# io-board-f-5.net
KiCad netlist of a schematic drawn in EAGLE
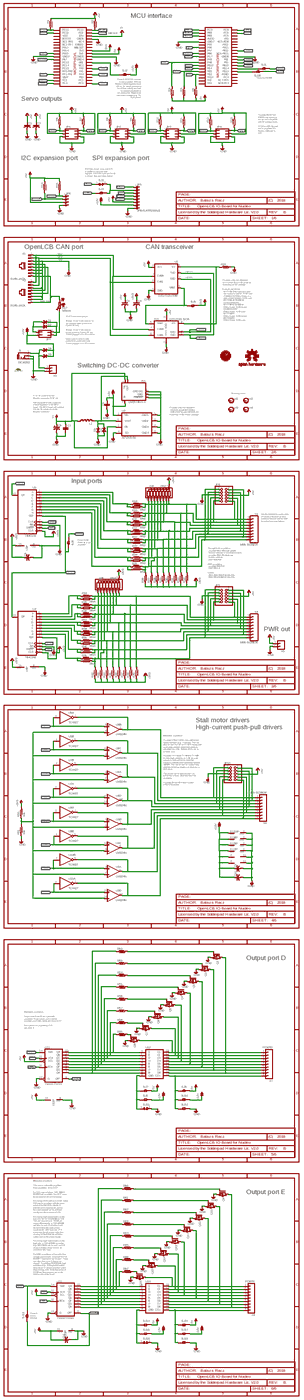
[diagram p0: schematic, sheet 1, overview]
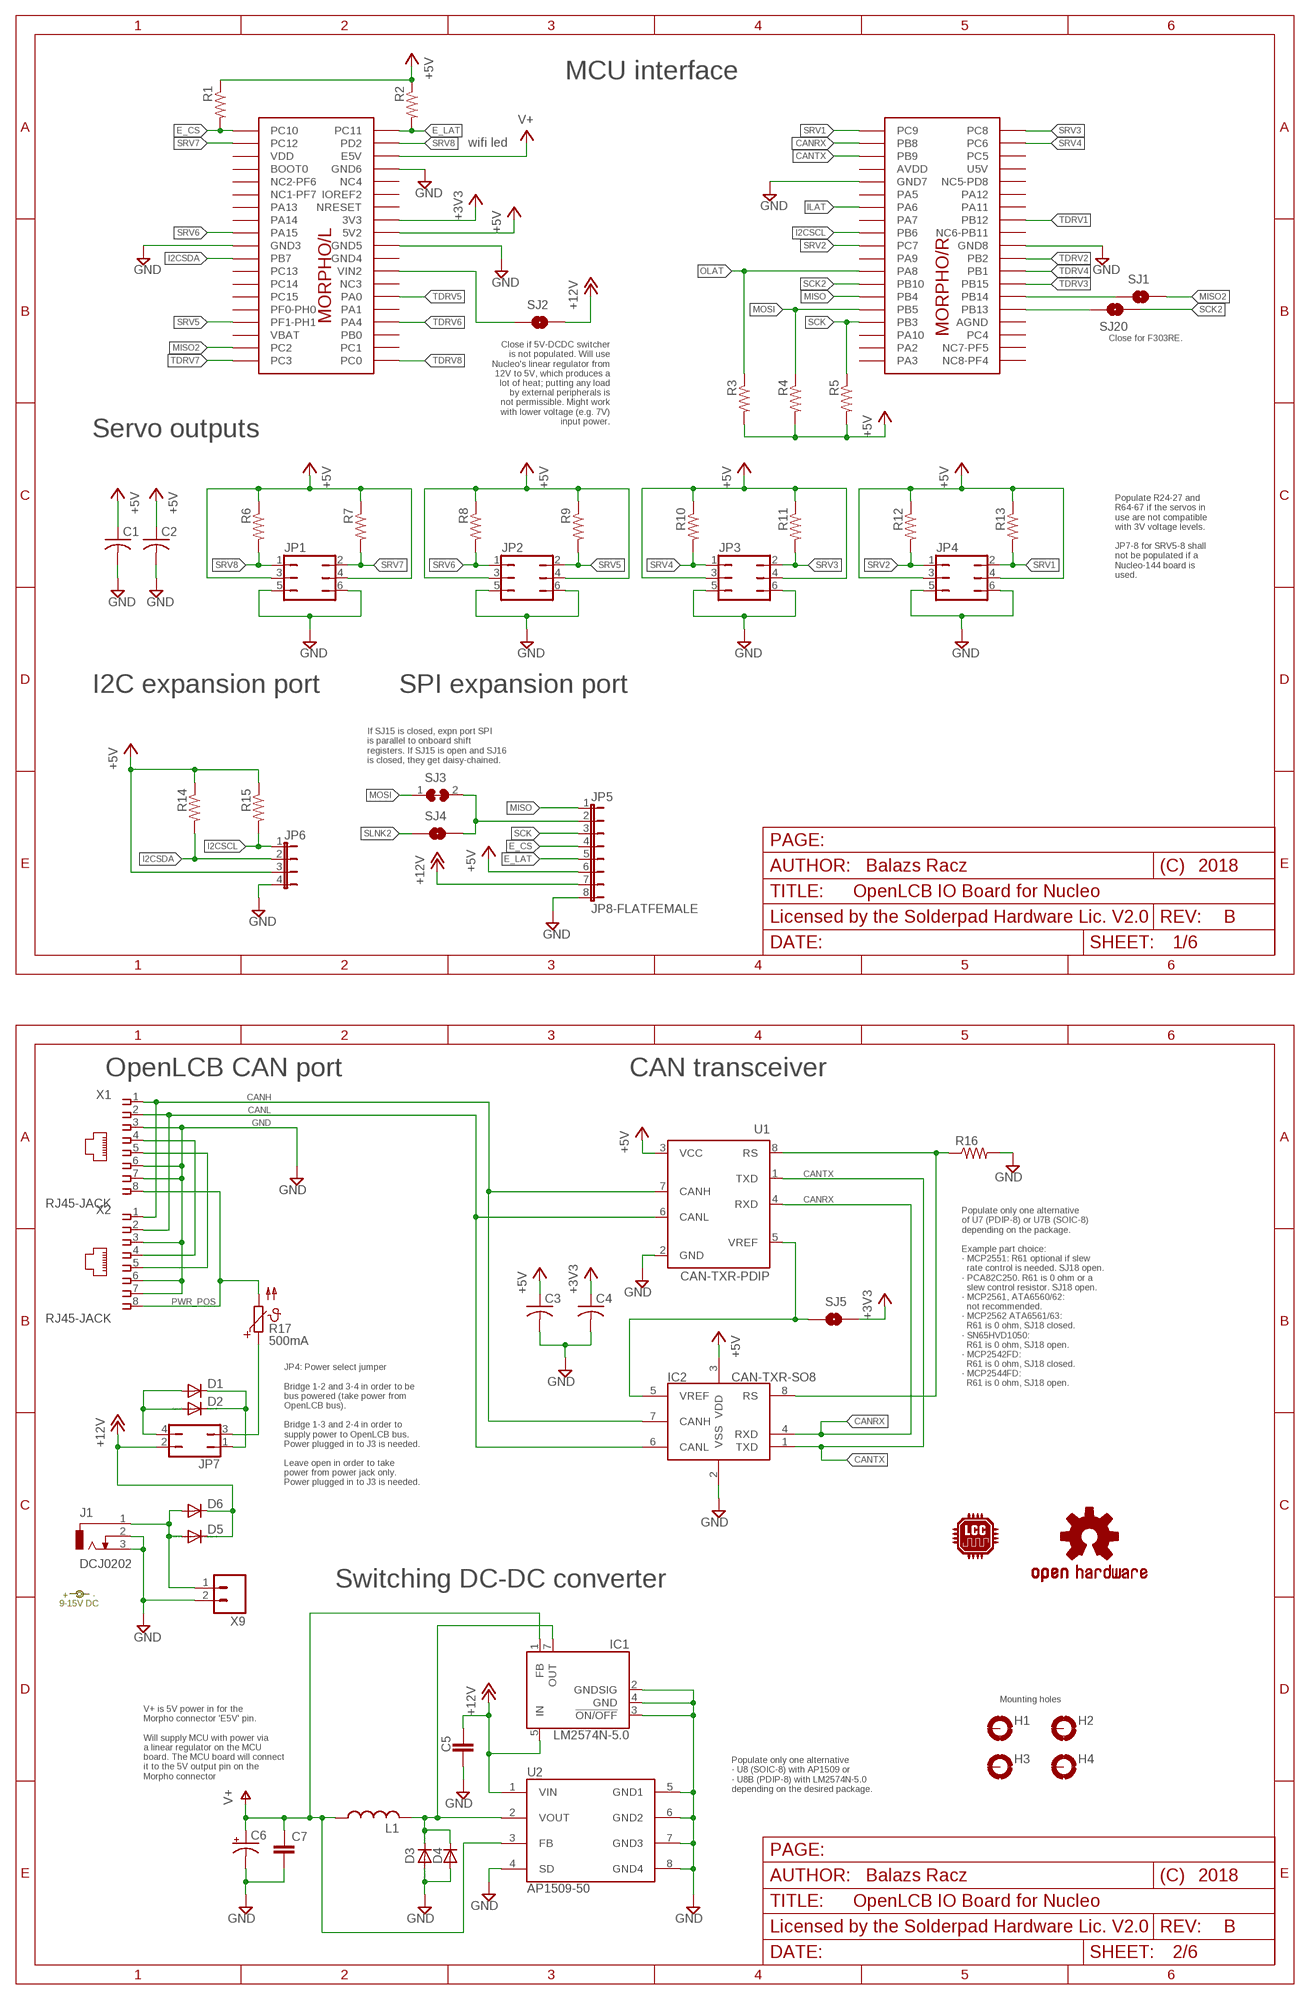
[diagram p1: schematic, sheet 1, part 1 of 4]
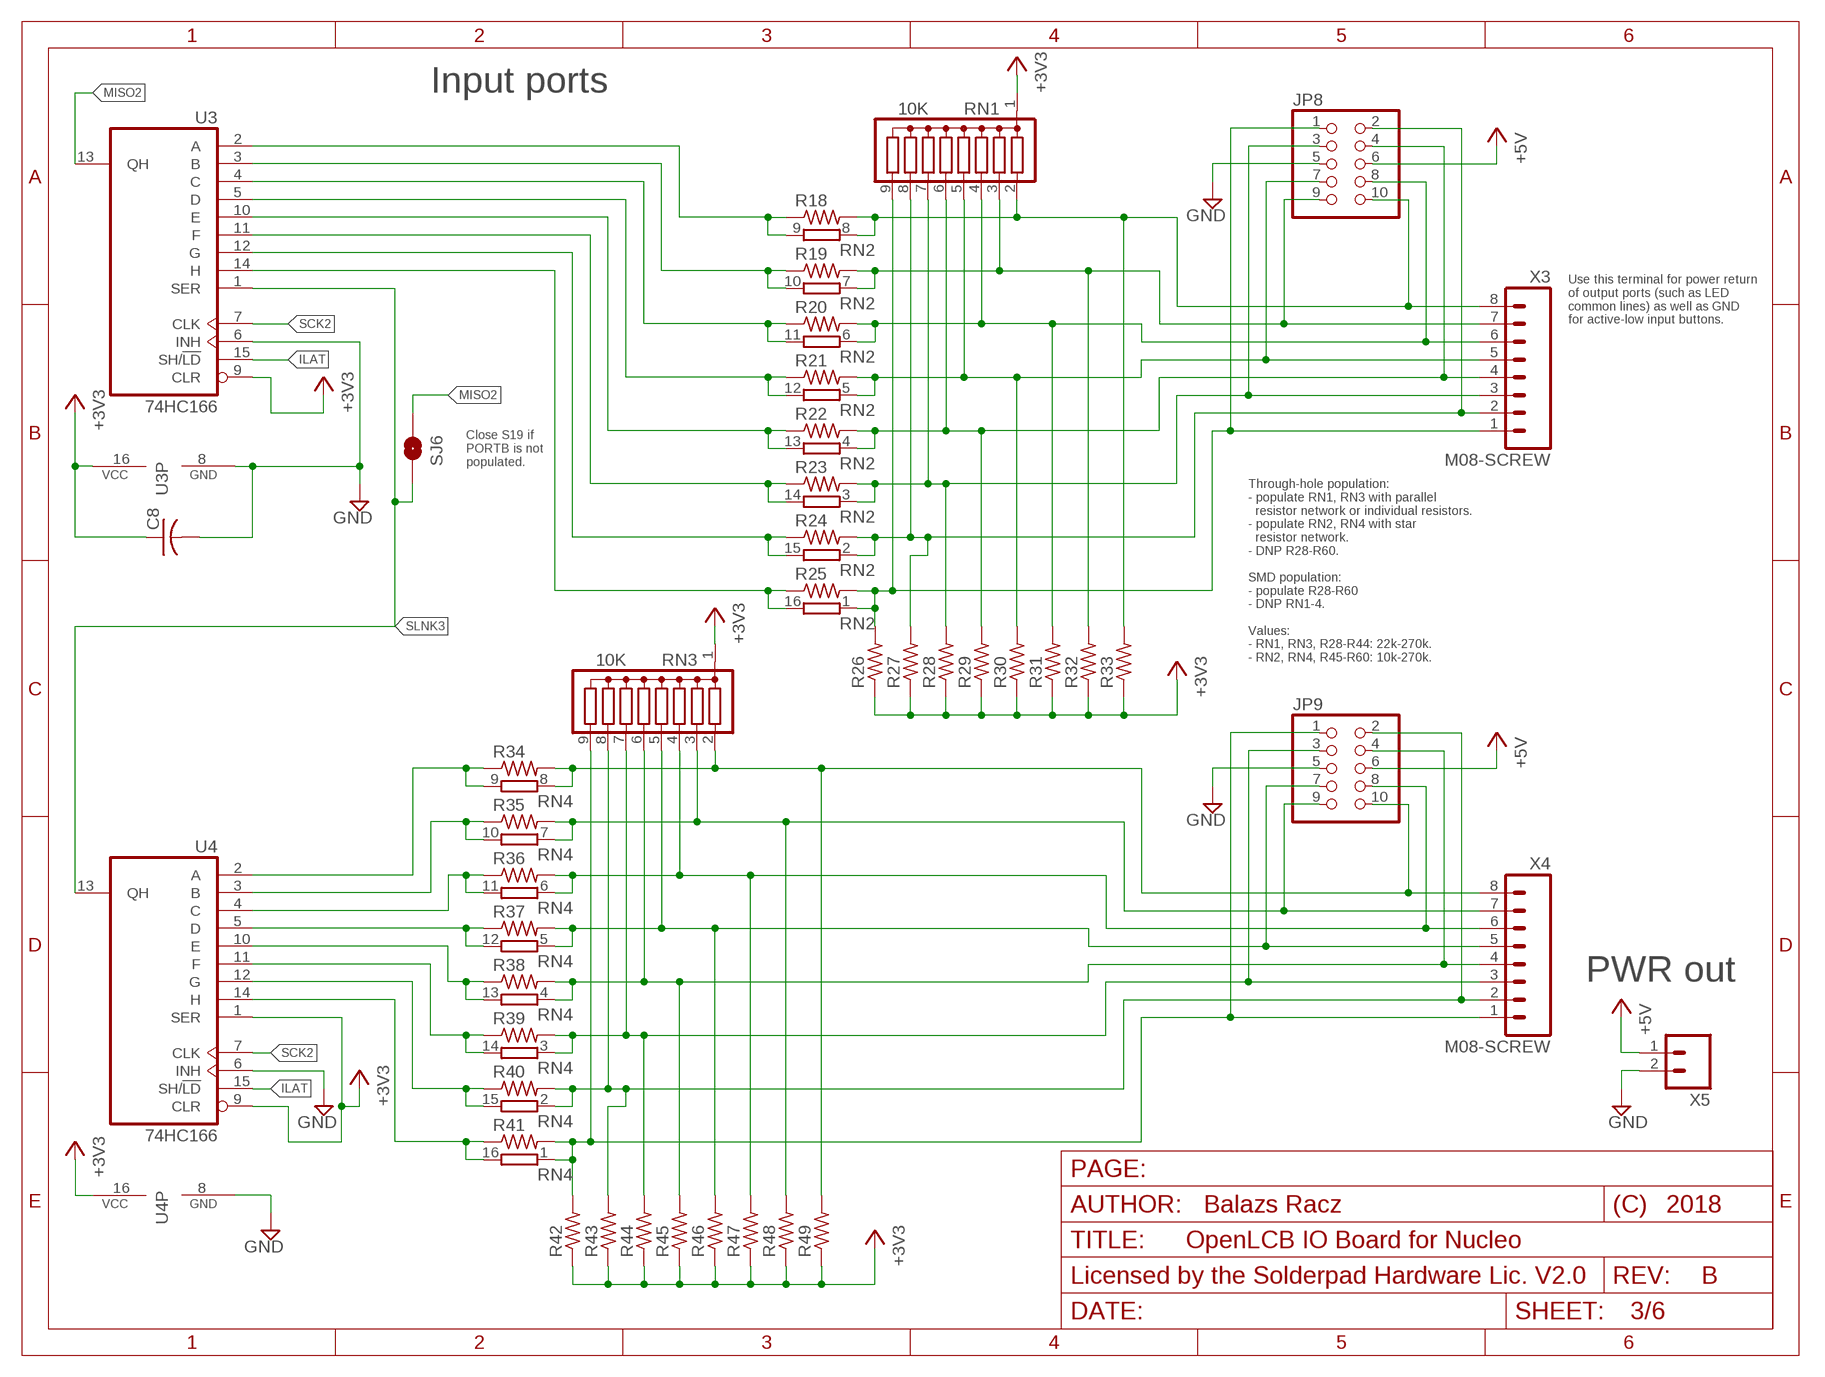
[diagram p2: schematic, sheet 1, part 2 of 4]
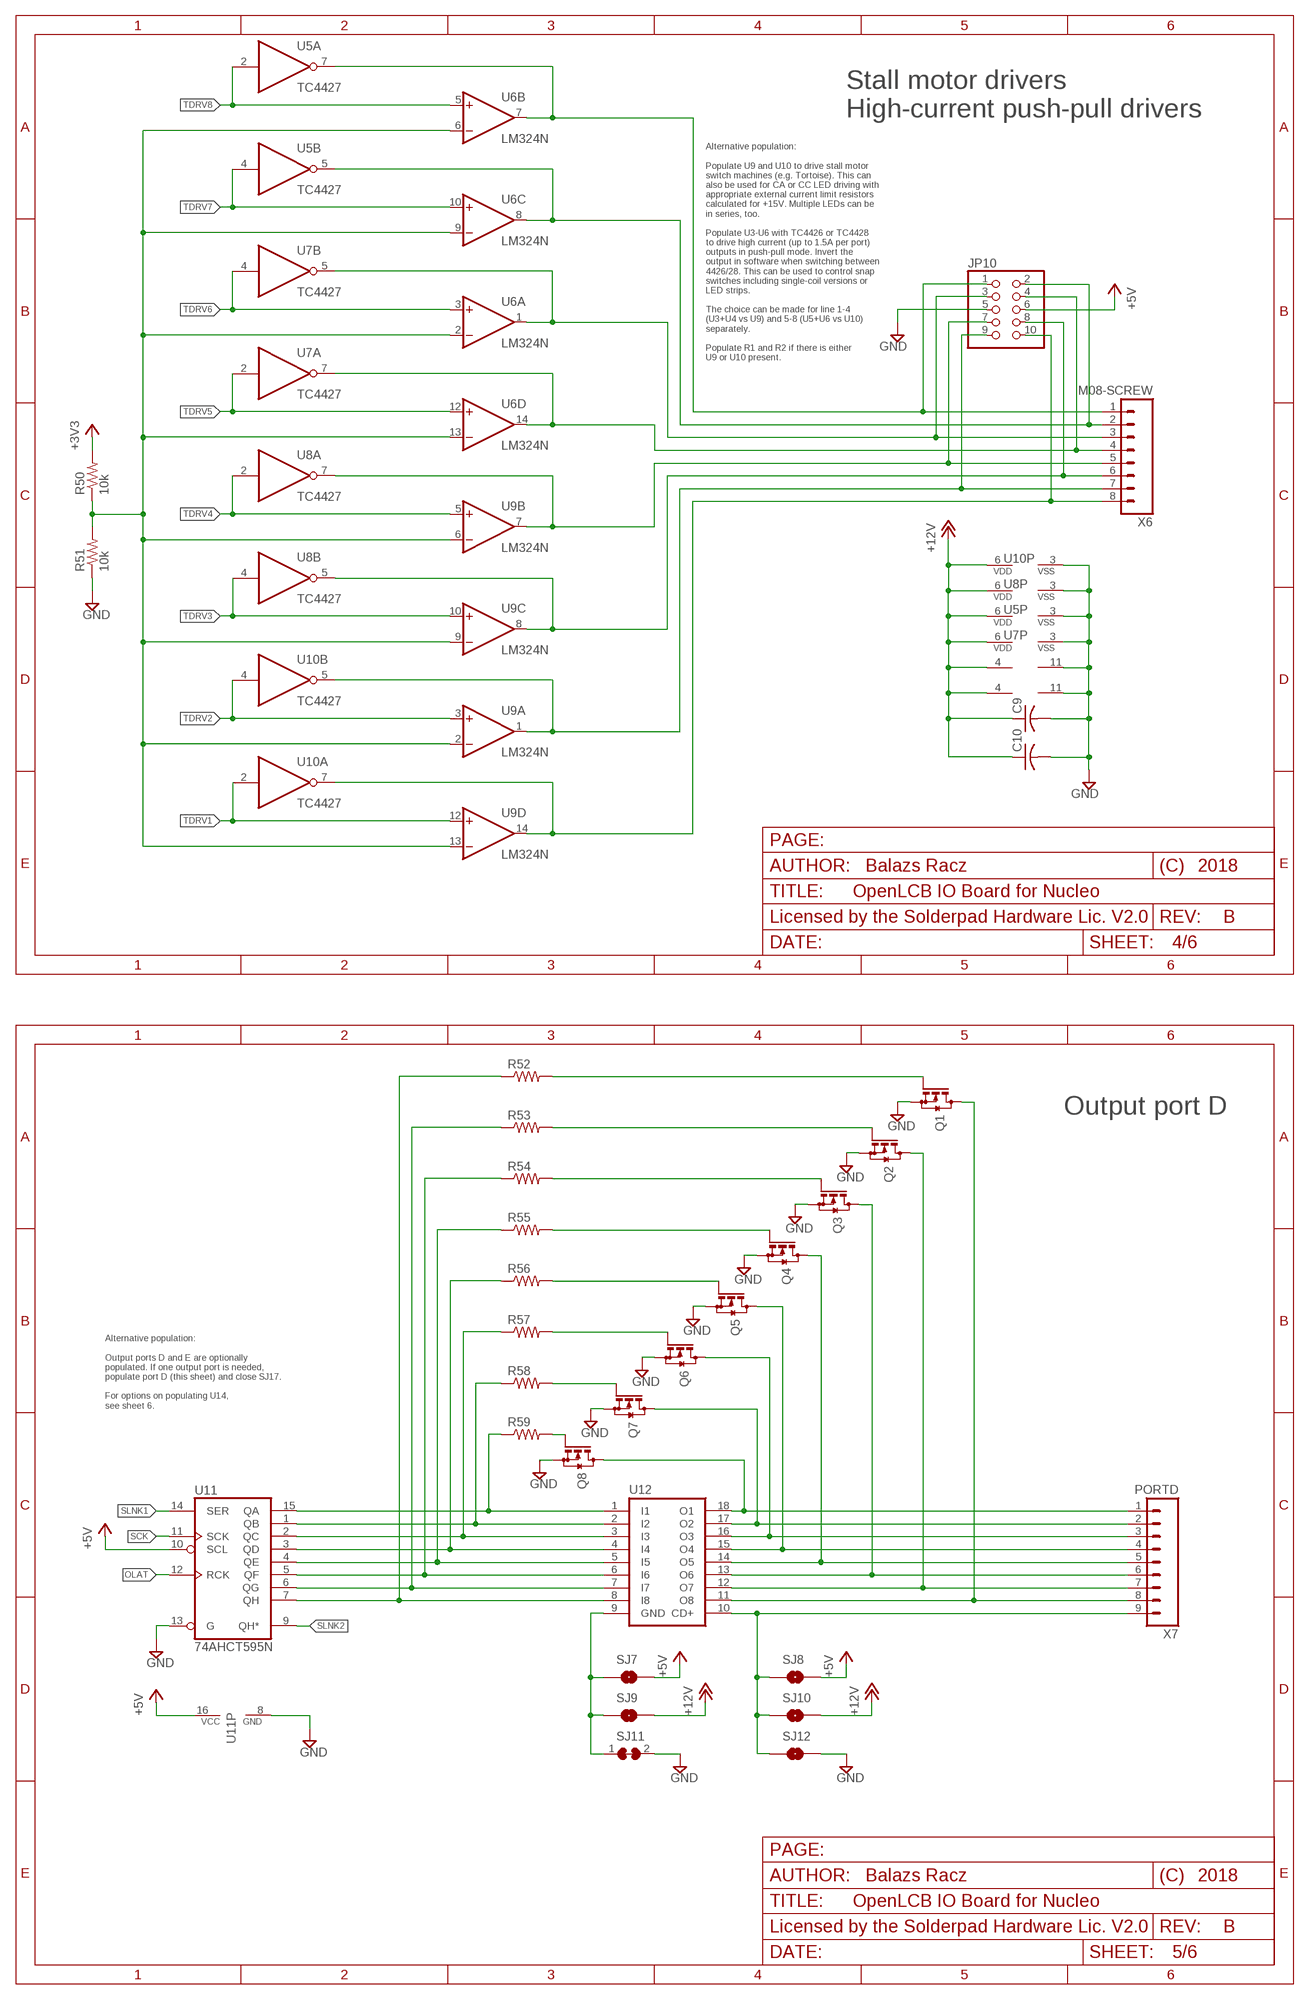
[diagram p3: schematic, sheet 1, part 3 of 4]
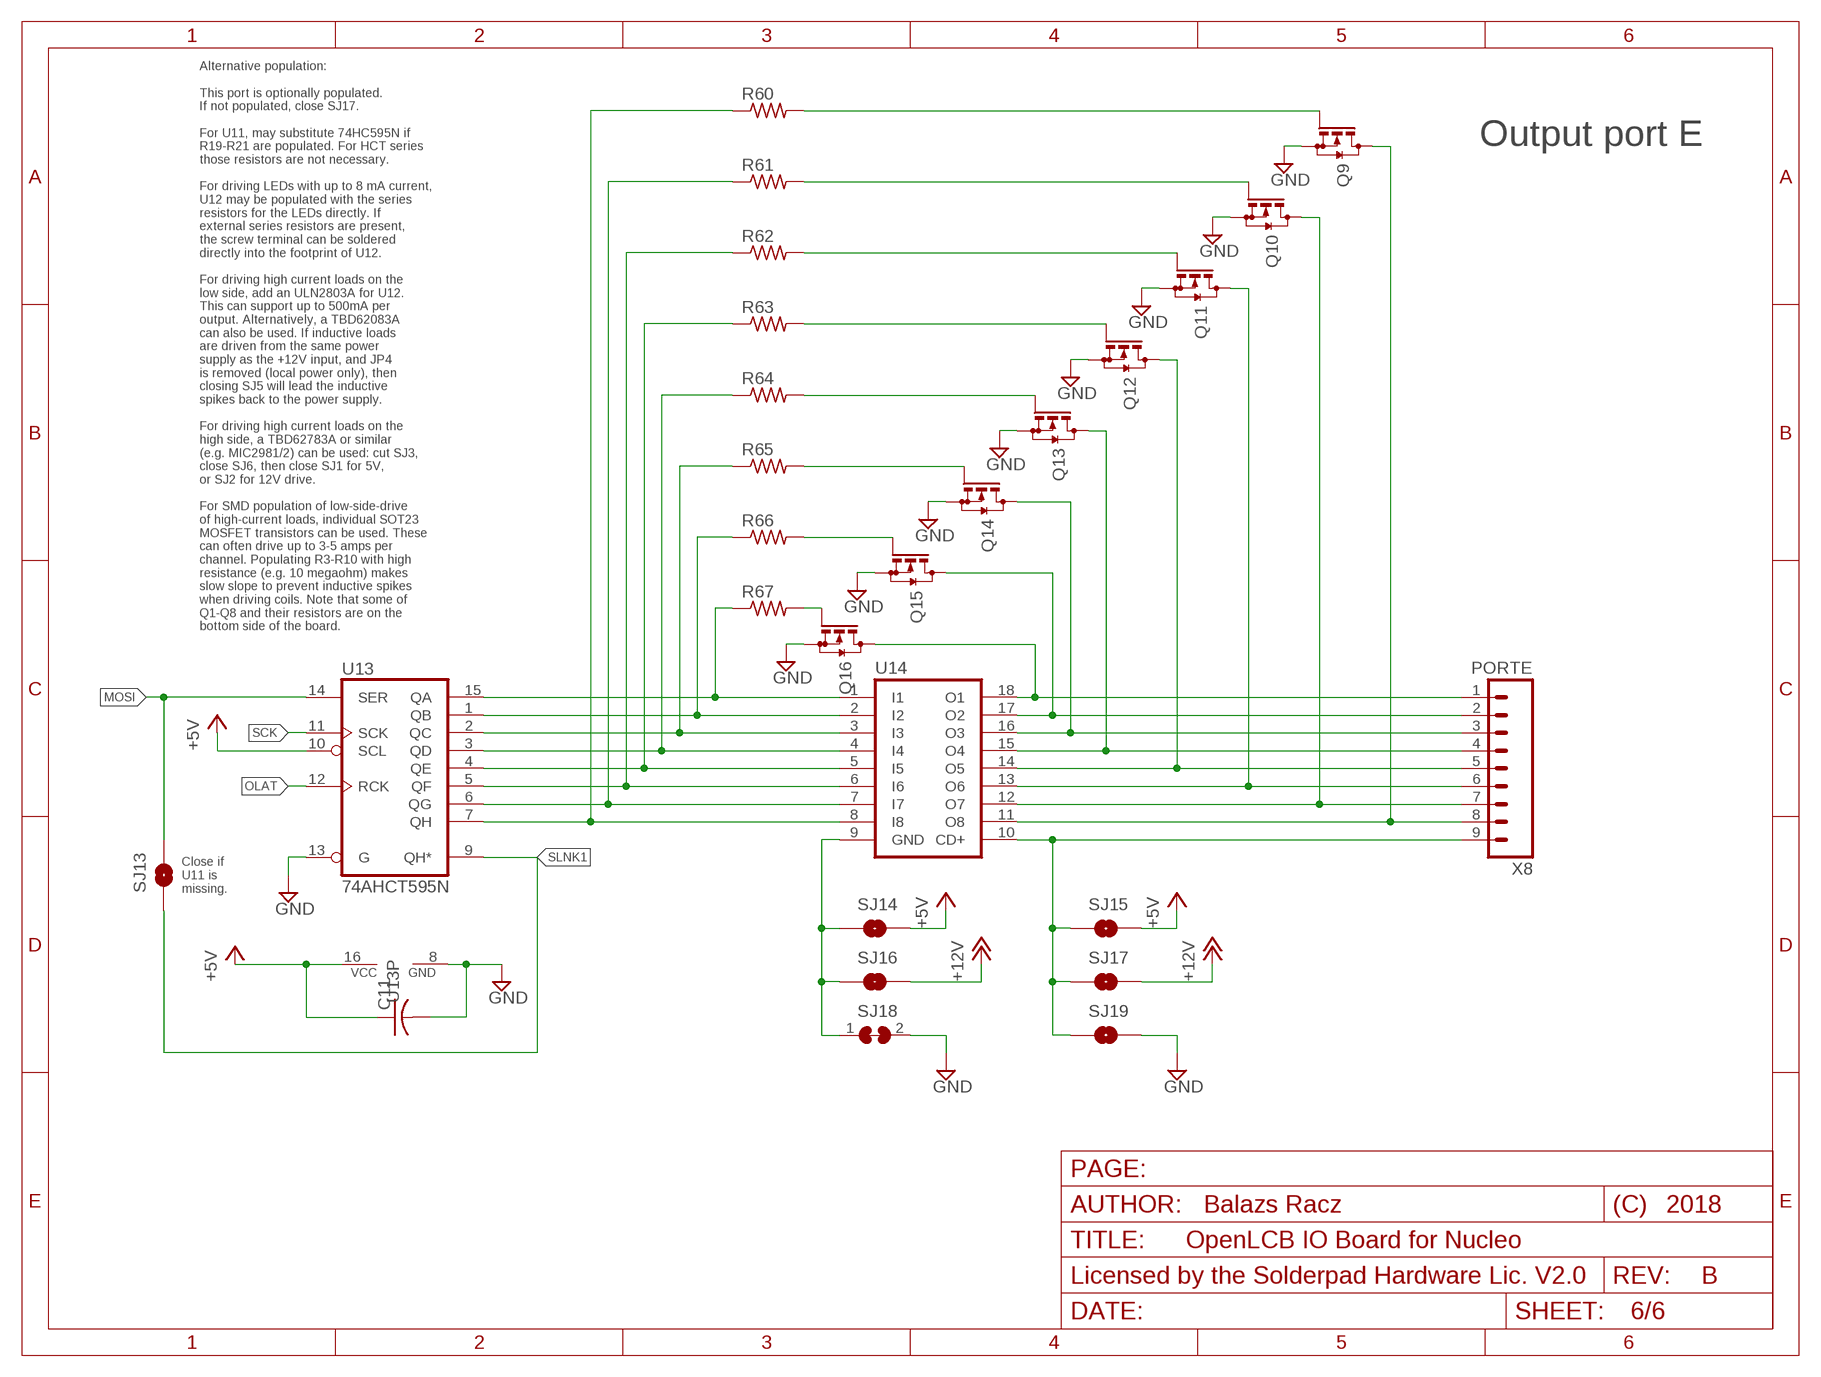
[diagram p4: schematic, sheet 1, part 4 of 4]

(export (version "E")
  (design (tool "Eeschema 10.0.6"))
  (components
    (comp (ref "C1")
      (value "C-USC1206")
      (footprint "eagle-import:C1206")
      (libsource (lib "eagle-import") (part "C-USC1206"))
    )
    (comp (ref "C2")
      (value "C-USC1206")
      (footprint "eagle-import:C1206")
      (libsource (lib "eagle-import") (part "C-USC1206"))
    )
    (comp (ref "C3")
      (value "C-USC0805")
      (footprint "eagle-import:C0805")
      (libsource (lib "eagle-import") (part "C-USC0805"))
    )
    (comp (ref "C4")
      (value "C-USC0805")
      (footprint "eagle-import:C0805")
      (libsource (lib "eagle-import") (part "C-USC0805"))
    )
    (comp (ref "C5")
      (value "C-EUC1206")
      (footprint "eagle-import:C1206")
      (libsource (lib "eagle-import") (part "C-EUC1206"))
    )
    (comp (ref "C6")
      (value "CPOL-USE2.5-5")
      (footprint "eagle-import:E2,5-5")
      (libsource (lib "eagle-import") (part "CPOL-USE2.5-5"))
    )
    (comp (ref "C7")
      (value "C-EUC1206")
      (footprint "eagle-import:C1206")
      (libsource (lib "eagle-import") (part "C-EUC1206"))
    )
    (comp (ref "C8")
      (value "C-USC0805")
      (footprint "eagle-import:C0805")
      (libsource (lib "eagle-import") (part "C-USC0805"))
    )
    (comp (ref "C9")
      (value "C-USC1206")
      (footprint "eagle-import:C1206")
      (libsource (lib "eagle-import") (part "C-USC1206"))
    )
    (comp (ref "C10")
      (value "C-USC1206")
      (footprint "eagle-import:C1206")
      (libsource (lib "eagle-import") (part "C-USC1206"))
    )
    (comp (ref "C11")
      (value "C-USC0805")
      (footprint "eagle-import:C0805")
      (libsource (lib "eagle-import") (part "C-USC0805"))
    )
    (comp (ref "D1")
      (value "DIODEDO-214AA-NODOC")
      (footprint "eagle-import:DO214AA-NODOC")
      (libsource (lib "eagle-import") (part "DIODEDO-214AA-NODOC"))
    )
    (comp (ref "D2")
      (value "DIODE-DO41-7.6")
      (footprint "eagle-import:DO41-7.6")
      (libsource (lib "eagle-import") (part "DIODE-DO41-7.6"))
    )
    (comp (ref "D3")
      (value "DIODE-DO41-7.6")
      (footprint "eagle-import:DO41-7.6")
      (libsource (lib "eagle-import") (part "DIODE-DO41-7.6"))
    )
    (comp (ref "D4")
      (value "DIODEDO-214AA-NODOC")
      (footprint "eagle-import:DO214AA-NODOC")
      (libsource (lib "eagle-import") (part "DIODEDO-214AA-NODOC"))
    )
    (comp (ref "D5")
      (value "DIODE-DO41-7.6")
      (footprint "eagle-import:DO41-7.6")
      (libsource (lib "eagle-import") (part "DIODE-DO41-7.6"))
    )
    (comp (ref "D6")
      (value "DIODEDO-214AA-NODOC")
      (footprint "eagle-import:DO214AA-NODOC")
      (libsource (lib "eagle-import") (part "DIODEDO-214AA-NODOC"))
    )
    (comp (ref "G1")
      (value "NUCLEO_64_GENERIC")
      (footprint "eagle-import:NUCLEO_BRD_BASE64")
      (libsource (lib "eagle-import") (part "NUCLEO_64_GENERIC"))
    )
    (comp (ref "H1")
      (value "MOUNT-PAD-ROUND3.3")
      (footprint "eagle-import:3,3-PAD")
      (libsource (lib "eagle-import") (part "MOUNT-PAD-ROUND3.3"))
    )
    (comp (ref "H2")
      (value "MOUNT-PAD-ROUND3.3")
      (footprint "eagle-import:3,3-PAD")
      (libsource (lib "eagle-import") (part "MOUNT-PAD-ROUND3.3"))
    )
    (comp (ref "H3")
      (value "MOUNT-PAD-ROUND3.3")
      (footprint "eagle-import:3,3-PAD")
      (libsource (lib "eagle-import") (part "MOUNT-PAD-ROUND3.3"))
    )
    (comp (ref "H4")
      (value "MOUNT-PAD-ROUND3.3")
      (footprint "eagle-import:3,3-PAD")
      (libsource (lib "eagle-import") (part "MOUNT-PAD-ROUND3.3"))
    )
    (comp (ref "IC1")
      (value "LM2574N-5.0")
      (footprint "eagle-import:DIL08")
      (libsource (lib "eagle-import") (part "LM2574?-N5.0"))
    )
    (comp (ref "IC2")
      (value "CAN-TXR-SO8")
      (footprint "eagle-import:SO-08")
      (libsource (lib "eagle-import") (part "MCP2551-SN"))
    )
    (comp (ref "J1")
      (value "DCJ0202")
      (footprint "eagle-import:DCJ0202")
      (libsource (lib "eagle-import") (part "DCJ0202"))
    )
    (comp (ref "JP1")
      (value "JP3Q")
      (footprint "eagle-import:JP3Q")
      (libsource (lib "eagle-import") (part "JP3Q"))
    )
    (comp (ref "JP2")
      (value "JP3Q")
      (footprint "eagle-import:JP3Q")
      (libsource (lib "eagle-import") (part "JP3Q"))
    )
    (comp (ref "JP3")
      (value "JP3Q")
      (footprint "eagle-import:JP3Q")
      (libsource (lib "eagle-import") (part "JP3Q"))
    )
    (comp (ref "JP4")
      (value "JP3Q")
      (footprint "eagle-import:JP3Q")
      (libsource (lib "eagle-import") (part "JP3Q"))
    )
    (comp (ref "JP5")
      (value "JP8-FLATFEMALE")
      (footprint "eagle-import:JP8F-FEM")
      (libsource (lib "eagle-import") (part "JP8-FLATFEMALE"))
    )
    (comp (ref "JP6")
      (value "JP4-FLAT")
      (footprint "eagle-import:JP4F")
      (libsource (lib "eagle-import") (part "JP4-FLAT"))
    )
    (comp (ref "JP7")
      (value "JP2Q")
      (footprint "eagle-import:JP2Q")
      (libsource (lib "eagle-import") (part "JP2Q"))
    )
    (comp (ref "JP8")
      (value "PINHD-2X5CN")
      (footprint "eagle-import:CON10M")
      (libsource (lib "eagle-import") (part "PINHD-2X5CN"))
    )
    (comp (ref "JP9")
      (value "PINHD-2X5CN")
      (footprint "eagle-import:CON10M")
      (libsource (lib "eagle-import") (part "PINHD-2X5CN"))
    )
    (comp (ref "JP10")
      (value "PINHD-2X5CN")
      (footprint "eagle-import:CON10M")
      (libsource (lib "eagle-import") (part "PINHD-2X5CN"))
    )
    (comp (ref "L1")
      (value "L-US")
      (footprint "eagle-import:L5-8,5")
      (libsource (lib "eagle-import") (part "L-US"))
    )
    (comp (ref "LG1")
      (value "LCC_LOGO")
      (footprint "eagle-import:LCC_LOGO")
      (libsource (lib "eagle-import") (part "LCC_LOGO"))
    )
    (comp (ref "LOGO1")
      (value "DOC-OSHW-LOGOM")
      (footprint "eagle-import:OSHW-LOGO-M")
      (libsource (lib "eagle-import") (part "DOC-OSHW-LOGOM"))
    )
    (comp (ref "P1")
      (value "9-15V DC")
      (footprint "eagle-import:POWER_USAGE")
      (libsource (lib "eagle-import") (part "DOC-POWER_LABEL"))
    )
    (comp (ref "Q1")
      (value "BSS123")
      (footprint "eagle-import:SOT23")
      (libsource (lib "eagle-import") (part "BSS123"))
    )
    (comp (ref "Q2")
      (value "BSS123")
      (footprint "eagle-import:SOT23")
      (libsource (lib "eagle-import") (part "BSS123"))
    )
    (comp (ref "Q3")
      (value "BSS123")
      (footprint "eagle-import:SOT23")
      (libsource (lib "eagle-import") (part "BSS123"))
    )
    (comp (ref "Q4")
      (value "BSS123")
      (footprint "eagle-import:SOT23")
      (libsource (lib "eagle-import") (part "BSS123"))
    )
    (comp (ref "Q5")
      (value "BSS123")
      (footprint "eagle-import:SOT23")
      (libsource (lib "eagle-import") (part "BSS123"))
    )
    (comp (ref "Q6")
      (value "BSS123")
      (footprint "eagle-import:SOT23")
      (libsource (lib "eagle-import") (part "BSS123"))
    )
    (comp (ref "Q7")
      (value "BSS123")
      (footprint "eagle-import:SOT23")
      (libsource (lib "eagle-import") (part "BSS123"))
    )
    (comp (ref "Q8")
      (value "BSS123")
      (footprint "eagle-import:SOT23")
      (libsource (lib "eagle-import") (part "BSS123"))
    )
    (comp (ref "Q9")
      (value "BSS123")
      (footprint "eagle-import:SOT23")
      (libsource (lib "eagle-import") (part "BSS123"))
    )
    (comp (ref "Q10")
      (value "BSS123")
      (footprint "eagle-import:SOT23")
      (libsource (lib "eagle-import") (part "BSS123"))
    )
    (comp (ref "Q11")
      (value "BSS123")
      (footprint "eagle-import:SOT23")
      (libsource (lib "eagle-import") (part "BSS123"))
    )
    (comp (ref "Q12")
      (value "BSS123")
      (footprint "eagle-import:SOT23")
      (libsource (lib "eagle-import") (part "BSS123"))
    )
    (comp (ref "Q13")
      (value "BSS123")
      (footprint "eagle-import:SOT23")
      (libsource (lib "eagle-import") (part "BSS123"))
    )
    (comp (ref "Q14")
      (value "BSS123")
      (footprint "eagle-import:SOT23")
      (libsource (lib "eagle-import") (part "BSS123"))
    )
    (comp (ref "Q15")
      (value "BSS123")
      (footprint "eagle-import:SOT23")
      (libsource (lib "eagle-import") (part "BSS123"))
    )
    (comp (ref "Q16")
      (value "BSS123")
      (footprint "eagle-import:SOT23")
      (libsource (lib "eagle-import") (part "BSS123"))
    )
    (comp (ref "R1")
      (value "R-US_R0805")
      (footprint "eagle-import:R0805")
      (libsource (lib "eagle-import") (part "rcl_334_R-US_R0805"))
    )
    (comp (ref "R2")
      (value "R-US_R0805")
      (footprint "eagle-import:R0805")
      (libsource (lib "eagle-import") (part "rcl_334_R-US_R0805"))
    )
    (comp (ref "R3")
      (value "R-US_R0805")
      (footprint "eagle-import:R0805")
      (libsource (lib "eagle-import") (part "rcl_334_R-US_R0805"))
    )
    (comp (ref "R4")
      (value "R-US_R0805")
      (footprint "eagle-import:R0805")
      (libsource (lib "eagle-import") (part "rcl_334_R-US_R0805"))
    )
    (comp (ref "R5")
      (value "R-US_R0805")
      (footprint "eagle-import:R0805")
      (libsource (lib "eagle-import") (part "rcl_334_R-US_R0805"))
    )
    (comp (ref "R6")
      (value "R-US_R0805")
      (footprint "eagle-import:R0805")
      (libsource (lib "eagle-import") (part "rcl_334_R-US_R0805"))
    )
    (comp (ref "R7")
      (value "R-US_R0805")
      (footprint "eagle-import:R0805")
      (libsource (lib "eagle-import") (part "rcl_334_R-US_R0805"))
    )
    (comp (ref "R8")
      (value "R-US_R0805")
      (footprint "eagle-import:R0805")
      (libsource (lib "eagle-import") (part "rcl_334_R-US_R0805"))
    )
    (comp (ref "R9")
      (value "R-US_R0805")
      (footprint "eagle-import:R0805")
      (libsource (lib "eagle-import") (part "rcl_334_R-US_R0805"))
    )
    (comp (ref "R10")
      (value "R-US_R0805")
      (footprint "eagle-import:R0805")
      (libsource (lib "eagle-import") (part "rcl_334_R-US_R0805"))
    )
    (comp (ref "R11")
      (value "R-US_R0805")
      (footprint "eagle-import:R0805")
      (libsource (lib "eagle-import") (part "rcl_334_R-US_R0805"))
    )
    (comp (ref "R12")
      (value "R-US_R0805")
      (footprint "eagle-import:R0805")
      (libsource (lib "eagle-import") (part "rcl_334_R-US_R0805"))
    )
    (comp (ref "R13")
      (value "R-US_R0805")
      (footprint "eagle-import:R0805")
      (libsource (lib "eagle-import") (part "rcl_334_R-US_R0805"))
    )
    (comp (ref "R14")
      (value "R-US_R0805")
      (footprint "eagle-import:R0805")
      (libsource (lib "eagle-import") (part "rcl_334_R-US_R0805"))
    )
    (comp (ref "R15")
      (value "R-US_R0805")
      (footprint "eagle-import:R0805")
      (libsource (lib "eagle-import") (part "rcl_334_R-US_R0805"))
    )
    (comp (ref "R16")
      (value "R-US_R0805")
      (footprint "eagle-import:R0805")
      (libsource (lib "eagle-import") (part "rcl_334_R-US_R0805"))
    )
    (comp (ref "R17")
      (value "500mA")
      (footprint "eagle-import:PTC1812")
      (libsource (lib "eagle-import") (part "PTC_1812"))
    )
    (comp (ref "R18")
      (value "R-US_R0603")
      (footprint "eagle-import:R0603")
      (libsource (lib "eagle-import") (part "rcl_334_R-US_R0603"))
    )
    (comp (ref "R19")
      (value "R-US_R0603")
      (footprint "eagle-import:R0603")
      (libsource (lib "eagle-import") (part "rcl_334_R-US_R0603"))
    )
    (comp (ref "R20")
      (value "R-US_R0603")
      (footprint "eagle-import:R0603")
      (libsource (lib "eagle-import") (part "rcl_334_R-US_R0603"))
    )
    (comp (ref "R21")
      (value "R-US_R0603")
      (footprint "eagle-import:R0603")
      (libsource (lib "eagle-import") (part "rcl_334_R-US_R0603"))
    )
    (comp (ref "R22")
      (value "R-US_R0603")
      (footprint "eagle-import:R0603")
      (libsource (lib "eagle-import") (part "rcl_334_R-US_R0603"))
    )
    (comp (ref "R23")
      (value "R-US_R0603")
      (footprint "eagle-import:R0603")
      (libsource (lib "eagle-import") (part "rcl_334_R-US_R0603"))
    )
    (comp (ref "R24")
      (value "R-US_R0603")
      (footprint "eagle-import:R0603")
      (libsource (lib "eagle-import") (part "rcl_334_R-US_R0603"))
    )
    (comp (ref "R25")
      (value "R-US_R0603")
      (footprint "eagle-import:R0603")
      (libsource (lib "eagle-import") (part "rcl_334_R-US_R0603"))
    )
    (comp (ref "R26")
      (value "R-US")
      (footprint "eagle-import:R0603")
      (libsource (lib "eagle-import") (part "R-US"))
    )
    (comp (ref "R27")
      (value "R-US")
      (footprint "eagle-import:R0603")
      (libsource (lib "eagle-import") (part "R-US"))
    )
    (comp (ref "R28")
      (value "R-US")
      (footprint "eagle-import:R0603")
      (libsource (lib "eagle-import") (part "R-US"))
    )
    (comp (ref "R29")
      (value "R-US")
      (footprint "eagle-import:R0603")
      (libsource (lib "eagle-import") (part "R-US"))
    )
    (comp (ref "R30")
      (value "R-US")
      (footprint "eagle-import:R0603")
      (libsource (lib "eagle-import") (part "R-US"))
    )
    (comp (ref "R31")
      (value "R-US")
      (footprint "eagle-import:R0603")
      (libsource (lib "eagle-import") (part "R-US"))
    )
    (comp (ref "R32")
      (value "R-US")
      (footprint "eagle-import:R0603")
      (libsource (lib "eagle-import") (part "R-US"))
    )
    (comp (ref "R33")
      (value "R-US")
      (footprint "eagle-import:R0603")
      (libsource (lib "eagle-import") (part "R-US"))
    )
    (comp (ref "R34")
      (value "R-US_R0603")
      (footprint "eagle-import:R0603")
      (libsource (lib "eagle-import") (part "rcl_334_R-US_R0603"))
    )
    (comp (ref "R35")
      (value "R-US_R0603")
      (footprint "eagle-import:R0603")
      (libsource (lib "eagle-import") (part "rcl_334_R-US_R0603"))
    )
    (comp (ref "R36")
      (value "R-US_R0603")
      (footprint "eagle-import:R0603")
      (libsource (lib "eagle-import") (part "rcl_334_R-US_R0603"))
    )
    (comp (ref "R37")
      (value "R-US_R0603")
      (footprint "eagle-import:R0603")
      (libsource (lib "eagle-import") (part "rcl_334_R-US_R0603"))
    )
    (comp (ref "R38")
      (value "R-US_R0603")
      (footprint "eagle-import:R0603")
      (libsource (lib "eagle-import") (part "rcl_334_R-US_R0603"))
    )
    (comp (ref "R39")
      (value "R-US_R0603")
      (footprint "eagle-import:R0603")
      (libsource (lib "eagle-import") (part "rcl_334_R-US_R0603"))
    )
    (comp (ref "R40")
      (value "R-US_R0603")
      (footprint "eagle-import:R0603")
      (libsource (lib "eagle-import") (part "rcl_334_R-US_R0603"))
    )
    (comp (ref "R41")
      (value "R-US_R0603")
      (footprint "eagle-import:R0603")
      (libsource (lib "eagle-import") (part "rcl_334_R-US_R0603"))
    )
    (comp (ref "R42")
      (value "R-US")
      (footprint "eagle-import:R0603")
      (libsource (lib "eagle-import") (part "R-US"))
    )
    (comp (ref "R43")
      (value "R-US")
      (footprint "eagle-import:R0603")
      (libsource (lib "eagle-import") (part "R-US"))
    )
    (comp (ref "R44")
      (value "R-US")
      (footprint "eagle-import:R0603")
      (libsource (lib "eagle-import") (part "R-US"))
    )
    (comp (ref "R45")
      (value "R-US")
      (footprint "eagle-import:R0603")
      (libsource (lib "eagle-import") (part "R-US"))
    )
    (comp (ref "R46")
      (value "R-US")
      (footprint "eagle-import:R0603")
      (libsource (lib "eagle-import") (part "R-US"))
    )
    (comp (ref "R47")
      (value "R-US")
      (footprint "eagle-import:R0603")
      (libsource (lib "eagle-import") (part "R-US"))
    )
    (comp (ref "R48")
      (value "R-US")
      (footprint "eagle-import:R0603")
      (libsource (lib "eagle-import") (part "R-US"))
    )
    (comp (ref "R49")
      (value "R-US")
      (footprint "eagle-import:R0603")
      (libsource (lib "eagle-import") (part "R-US"))
    )
    (comp (ref "R50")
      (value "10k")
      (footprint "eagle-import:R0805")
      (libsource (lib "eagle-import") (part "R-US_R0805"))
    )
    (comp (ref "R51")
      (value "10k")
      (footprint "eagle-import:R0805")
      (libsource (lib "eagle-import") (part "R-US_R0805"))
    )
    (comp (ref "R52")
      (value "R-US_R0603")
      (footprint "eagle-import:R0603")
      (libsource (lib "eagle-import") (part "R-US_R0603"))
    )
    (comp (ref "R53")
      (value "R-US_R0603")
      (footprint "eagle-import:R0603")
      (libsource (lib "eagle-import") (part "R-US_R0603"))
    )
    (comp (ref "R54")
      (value "R-US_R0603")
      (footprint "eagle-import:R0603")
      (libsource (lib "eagle-import") (part "R-US_R0603"))
    )
    (comp (ref "R55")
      (value "R-US_R0603")
      (footprint "eagle-import:R0603")
      (libsource (lib "eagle-import") (part "R-US_R0603"))
    )
    (comp (ref "R56")
      (value "R-US_R0603")
      (footprint "eagle-import:R0603")
      (libsource (lib "eagle-import") (part "R-US_R0603"))
    )
    (comp (ref "R57")
      (value "R-US_R0603")
      (footprint "eagle-import:R0603")
      (libsource (lib "eagle-import") (part "R-US_R0603"))
    )
    (comp (ref "R58")
      (value "R-US_R0603")
      (footprint "eagle-import:R0603")
      (libsource (lib "eagle-import") (part "R-US_R0603"))
    )
    (comp (ref "R59")
      (value "R-US_R0603")
      (footprint "eagle-import:R0603")
      (libsource (lib "eagle-import") (part "R-US_R0603"))
    )
    (comp (ref "R60")
      (value "R-US_R0603")
      (footprint "eagle-import:R0603")
      (libsource (lib "eagle-import") (part "R-US_R0603"))
    )
    (comp (ref "R61")
      (value "R-US_R0603")
      (footprint "eagle-import:R0603")
      (libsource (lib "eagle-import") (part "R-US_R0603"))
    )
    (comp (ref "R62")
      (value "R-US_R0603")
      (footprint "eagle-import:R0603")
      (libsource (lib "eagle-import") (part "R-US_R0603"))
    )
    (comp (ref "R63")
      (value "R-US_R0603")
      (footprint "eagle-import:R0603")
      (libsource (lib "eagle-import") (part "R-US_R0603"))
    )
    (comp (ref "R64")
      (value "R-US_R0603")
      (footprint "eagle-import:R0603")
      (libsource (lib "eagle-import") (part "R-US_R0603"))
    )
    (comp (ref "R65")
      (value "R-US_R0603")
      (footprint "eagle-import:R0603")
      (libsource (lib "eagle-import") (part "R-US_R0603"))
    )
    (comp (ref "R66")
      (value "R-US_R0603")
      (footprint "eagle-import:R0603")
      (libsource (lib "eagle-import") (part "R-US_R0603"))
    )
    (comp (ref "R67")
      (value "R-US_R0603")
      (footprint "eagle-import:R0603")
      (libsource (lib "eagle-import") (part "R-US_R0603"))
    )
    (comp (ref "RN1")
      (value "10K")
      (footprint "eagle-import:SIL9")
      (libsource (lib "eagle-import") (part "G08R"))
    )
    (comp (ref "RN2")
      (value "8R-P")
      (footprint "eagle-import:DIL16")
      (libsource (lib "eagle-import") (part "8R-P"))
    )
    (comp (ref "RN3")
      (value "10K")
      (footprint "eagle-import:SIL9")
      (libsource (lib "eagle-import") (part "G08R"))
    )
    (comp (ref "RN4")
      (value "8R-P")
      (footprint "eagle-import:DIL16")
      (libsource (lib "eagle-import") (part "8R-P"))
    )
    (comp (ref "SJ1")
      (value "SJRND2")
      (footprint "eagle-import:SJ_RND2")
      (libsource (lib "eagle-import") (part "SJRND2"))
    )
    (comp (ref "SJ2")
      (value "SJRND2")
      (footprint "eagle-import:SJ_RND2")
      (libsource (lib "eagle-import") (part "SJRND2"))
    )
    (comp (ref "SJ3")
      (value "SJ-C")
      (footprint "eagle-import:SJW-C")
      (libsource (lib "eagle-import") (part "SJ-C"))
    )
    (comp (ref "SJ4")
      (value "SJRND2")
      (footprint "eagle-import:SJ_RND2")
      (libsource (lib "eagle-import") (part "SJRND2"))
    )
    (comp (ref "SJ5")
      (value "SJRND2")
      (footprint "eagle-import:SJ_RND2")
      (libsource (lib "eagle-import") (part "SJRND2"))
    )
    (comp (ref "SJ6")
      (value "SJRND2")
      (footprint "eagle-import:SJ_RND2")
      (libsource (lib "eagle-import") (part "SJRND2"))
    )
    (comp (ref "SJ7")
      (value "SJRND2")
      (footprint "eagle-import:SJ_RND2")
      (libsource (lib "eagle-import") (part "SJRND2"))
    )
    (comp (ref "SJ8")
      (value "SJRND2")
      (footprint "eagle-import:SJ_RND2")
      (libsource (lib "eagle-import") (part "SJRND2"))
    )
    (comp (ref "SJ9")
      (value "SJRND2")
      (footprint "eagle-import:SJ_RND2")
      (libsource (lib "eagle-import") (part "SJRND2"))
    )
    (comp (ref "SJ10")
      (value "SJRND2")
      (footprint "eagle-import:SJ_RND2")
      (libsource (lib "eagle-import") (part "SJRND2"))
    )
    (comp (ref "SJ11")
      (value "SJ-C")
      (footprint "eagle-import:SJW-C")
      (libsource (lib "eagle-import") (part "SJ-C"))
    )
    (comp (ref "SJ12")
      (value "SJRND2")
      (footprint "eagle-import:SJ_RND2")
      (libsource (lib "eagle-import") (part "SJRND2"))
    )
    (comp (ref "SJ13")
      (value "SJRND2")
      (footprint "eagle-import:SJ_RND2")
      (libsource (lib "eagle-import") (part "SJRND2"))
    )
    (comp (ref "SJ14")
      (value "SJRND2")
      (footprint "eagle-import:SJ_RND2")
      (libsource (lib "eagle-import") (part "SJRND2"))
    )
    (comp (ref "SJ15")
      (value "SJRND2")
      (footprint "eagle-import:SJ_RND2")
      (libsource (lib "eagle-import") (part "SJRND2"))
    )
    (comp (ref "SJ16")
      (value "SJRND2")
      (footprint "eagle-import:SJ_RND2")
      (libsource (lib "eagle-import") (part "SJRND2"))
    )
    (comp (ref "SJ17")
      (value "SJRND2")
      (footprint "eagle-import:SJ_RND2")
      (libsource (lib "eagle-import") (part "SJRND2"))
    )
    (comp (ref "SJ18")
      (value "SJ-C")
      (footprint "eagle-import:SJW-C")
      (libsource (lib "eagle-import") (part "SJ-C"))
    )
    (comp (ref "SJ19")
      (value "SJRND2")
      (footprint "eagle-import:SJ_RND2")
      (libsource (lib "eagle-import") (part "SJRND2"))
    )
    (comp (ref "SJ20")
      (value "SJRND2")
      (footprint "eagle-import:SJ_RND2")
      (libsource (lib "eagle-import") (part "SJRND2"))
    )
    (comp (ref "U1")
      (value "CAN-TXR-PDIP")
      (footprint "eagle-import:DIL08")
      (libsource (lib "eagle-import") (part "PCA82C250"))
    )
    (comp (ref "U2")
      (value "AP1509-50")
      (footprint "eagle-import:SO-08")
      (libsource (lib "eagle-import") (part "AP1509"))
    )
    (comp (ref "U3")
      (value "74HC166")
      (footprint "eagle-import:DIL16")
      (libsource (lib "eagle-import") (part "74166N"))
    )
    (comp (ref "U4")
      (value "74HC166")
      (footprint "eagle-import:DIL16")
      (libsource (lib "eagle-import") (part "74166N"))
    )
    (comp (ref "U5")
      (value "TC4427")
      (footprint "eagle-import:DIL08-LONG")
      (libsource (lib "eagle-import") (part "TC4426APDIP"))
    )
    (comp (ref "U6")
      (value "LM324N")
      (footprint "eagle-import:DIL14")
      (libsource (lib "eagle-import") (part "LM324N"))
    )
    (comp (ref "U7")
      (value "TC4427")
      (footprint "eagle-import:DIL08-LONG")
      (libsource (lib "eagle-import") (part "TC4426APDIP"))
    )
    (comp (ref "U8")
      (value "TC4427")
      (footprint "eagle-import:DIL08-LONG")
      (libsource (lib "eagle-import") (part "TC4426APDIP"))
    )
    (comp (ref "U9")
      (value "LM324N")
      (footprint "eagle-import:DIL14")
      (libsource (lib "eagle-import") (part "LM324N"))
    )
    (comp (ref "U10")
      (value "TC4427")
      (footprint "eagle-import:DIL08-LONG")
      (libsource (lib "eagle-import") (part "TC4426APDIP"))
    )
    (comp (ref "U11")
      (value "74AHCT595N")
      (footprint "eagle-import:DIL16")
      (libsource (lib "eagle-import") (part "74595NHCT"))
    )
    (comp (ref "U12")
      (value "ULN2803A")
      (footprint "eagle-import:DIL18-THIN")
      (libsource (lib "eagle-import") (part "ULN2803A"))
    )
    (comp (ref "U13")
      (value "74AHCT595N")
      (footprint "eagle-import:DIL16")
      (libsource (lib "eagle-import") (part "74595NHCT"))
    )
    (comp (ref "U14")
      (value "ULN2803A")
      (footprint "eagle-import:DIL18-THIN")
      (libsource (lib "eagle-import") (part "ULN2803A"))
    )
    (comp (ref "X1")
      (value "RJ45-JACK")
      (footprint "eagle-import:RJ45-PULSE-E5J88")
      (libsource (lib "eagle-import") (part "RJ45-JACKRJ45-PULSE-E5J00"))
    )
    (comp (ref "X2")
      (value "RJ45-JACK")
      (footprint "eagle-import:RJ45-PULSE-E5J88")
      (libsource (lib "eagle-import") (part "RJ45-JACKRJ45-PULSE-E5J00"))
    )
    (comp (ref "X3")
      (value "M08-SCREW")
      (footprint "eagle-import:1X08_TERMINAL")
      (libsource (lib "eagle-import") (part "M08-SCREW"))
    )
    (comp (ref "X4")
      (value "M08-SCREW")
      (footprint "eagle-import:1X08_TERMINAL")
      (libsource (lib "eagle-import") (part "M08-SCREW"))
    )
    (comp (ref "X5")
      (value "CONNECTOR-M023.5MM-LOCK")
      (footprint "eagle-import:SCREWTERMINAL-3.5MM-2_LOCK")
      (libsource (lib "eagle-import") (part "CONNECTOR-M023.5MM-LOCK"))
    )
    (comp (ref "X6")
      (value "M08-SCREW")
      (footprint "eagle-import:1X08_TERMINAL")
      (libsource (lib "eagle-import") (part "M08-SCREW"))
    )
    (comp (ref "X7")
      (value "PORTD")
      (footprint "eagle-import:1X09_TERMINAL")
      (libsource (lib "eagle-import") (part "M09-SCREW"))
    )
    (comp (ref "X8")
      (value "PORTE")
      (footprint "eagle-import:1X09_TERMINAL")
      (libsource (lib "eagle-import") (part "M09-SCREW"))
    )
    (comp (ref "X9")
      (value "CONNECTOR-M023.5MM-LOCK")
      (footprint "eagle-import:SCREWTERMINAL-3.5MM-2_LOCK")
      (libsource (lib "eagle-import") (part "CONNECTOR-M023.5MM-LOCK"))
    )
  )
  (nets
    (net (code "1") (name "+3V3") (class "Default")
      (node (ref "C4") (pin "1") (pinfunction "1_1") (pintype "passive"))
      (node (ref "C8") (pin "1") (pinfunction "1_1") (pintype "passive"))
      (node (ref "G1") (pin "3V3") (pinfunction "3V3_3V3") (pintype "power_in"))
      (node (ref "R26") (pin "1") (pinfunction "1_1") (pintype "passive"))
      (node (ref "R27") (pin "1") (pinfunction "1_1") (pintype "passive"))
      (node (ref "R28") (pin "1") (pinfunction "1_1") (pintype "passive"))
      (node (ref "R29") (pin "1") (pinfunction "1_1") (pintype "passive"))
      (node (ref "R30") (pin "1") (pinfunction "1_1") (pintype "passive"))
      (node (ref "R31") (pin "1") (pinfunction "1_1") (pintype "passive"))
      (node (ref "R32") (pin "1") (pinfunction "1_1") (pintype "passive"))
      (node (ref "R33") (pin "1") (pinfunction "1_1") (pintype "passive"))
      (node (ref "R42") (pin "1") (pinfunction "1_1") (pintype "passive"))
      (node (ref "R43") (pin "1") (pinfunction "1_1") (pintype "passive"))
      (node (ref "R44") (pin "1") (pinfunction "1_1") (pintype "passive"))
      (node (ref "R45") (pin "1") (pinfunction "1_1") (pintype "passive"))
      (node (ref "R46") (pin "1") (pinfunction "1_1") (pintype "passive"))
      (node (ref "R47") (pin "1") (pinfunction "1_1") (pintype "passive"))
      (node (ref "R48") (pin "1") (pinfunction "1_1") (pintype "passive"))
      (node (ref "R49") (pin "1") (pinfunction "1_1") (pintype "passive"))
      (node (ref "R50") (pin "2") (pinfunction "2_2") (pintype "passive"))
      (node (ref "RN1") (pin "1") (pinfunction "1_1") (pintype "passive"))
      (node (ref "RN3") (pin "1") (pinfunction "1_1") (pintype "passive"))
      (node (ref "SJ5") (pin "P$1") (pinfunction "1_P$1") (pintype "passive"))
      (node (ref "U3") (pin "16") (pinfunction "VCC_16") (pintype "power_in"))
      (node (ref "U3") (pin "9") (pinfunction "CLR_9") (pintype "input"))
      (node (ref "U4") (pin "1") (pinfunction "SER_1") (pintype "input"))
      (node (ref "U4") (pin "16") (pinfunction "VCC_16") (pintype "power_in"))
      (node (ref "U4") (pin "9") (pinfunction "CLR_9") (pintype "input"))
    )
    (net (code "2") (name "+5V") (class "Default")
      (node (ref "C1") (pin "1") (pinfunction "1_1") (pintype "passive"))
      (node (ref "C11") (pin "1") (pinfunction "1_1") (pintype "passive"))
      (node (ref "C2") (pin "1") (pinfunction "1_1") (pintype "passive"))
      (node (ref "C3") (pin "1") (pinfunction "1_1") (pintype "passive"))
      (node (ref "G1") (pin "5V2") (pinfunction "5V2_5V2") (pintype "power_in"))
      (node (ref "IC2") (pin "3") (pinfunction "VDD_3") (pintype "power_in"))
      (node (ref "JP1") (pin "3") (pinfunction "3_3") (pintype "passive"))
      (node (ref "JP1") (pin "4") (pinfunction "4_4") (pintype "passive"))
      (node (ref "JP10") (pin "6") (pinfunction "6_6") (pintype "passive"))
      (node (ref "JP2") (pin "3") (pinfunction "3_3") (pintype "passive"))
      (node (ref "JP2") (pin "4") (pinfunction "4_4") (pintype "passive"))
      (node (ref "JP3") (pin "3") (pinfunction "3_3") (pintype "passive"))
      (node (ref "JP3") (pin "4") (pinfunction "4_4") (pintype "passive"))
      (node (ref "JP4") (pin "3") (pinfunction "3_3") (pintype "passive"))
      (node (ref "JP4") (pin "4") (pinfunction "4_4") (pintype "passive"))
      (node (ref "JP5") (pin "6") (pinfunction "6_6") (pintype "passive"))
      (node (ref "JP6") (pin "3") (pinfunction "3_3") (pintype "passive"))
      (node (ref "JP8") (pin "6") (pinfunction "6_6") (pintype "passive"))
      (node (ref "JP9") (pin "6") (pinfunction "6_6") (pintype "passive"))
      (node (ref "R1") (pin "1") (pinfunction "1_1") (pintype "passive"))
      (node (ref "R10") (pin "1") (pinfunction "1_1") (pintype "passive"))
      (node (ref "R11") (pin "1") (pinfunction "1_1") (pintype "passive"))
      (node (ref "R12") (pin "1") (pinfunction "1_1") (pintype "passive"))
      (node (ref "R13") (pin "1") (pinfunction "1_1") (pintype "passive"))
      (node (ref "R14") (pin "1") (pinfunction "1_1") (pintype "passive"))
      (node (ref "R15") (pin "1") (pinfunction "1_1") (pintype "passive"))
      (node (ref "R2") (pin "1") (pinfunction "1_1") (pintype "passive"))
      (node (ref "R3") (pin "2") (pinfunction "2_2") (pintype "passive"))
      (node (ref "R4") (pin "2") (pinfunction "2_2") (pintype "passive"))
      (node (ref "R5") (pin "2") (pinfunction "2_2") (pintype "passive"))
      (node (ref "R6") (pin "1") (pinfunction "1_1") (pintype "passive"))
      (node (ref "R7") (pin "1") (pinfunction "1_1") (pintype "passive"))
      (node (ref "R8") (pin "1") (pinfunction "1_1") (pintype "passive"))
      (node (ref "R9") (pin "1") (pinfunction "1_1") (pintype "passive"))
      (node (ref "SJ14") (pin "P$2") (pinfunction "2_P$2") (pintype "passive"))
      (node (ref "SJ15") (pin "P$2") (pinfunction "2_P$2") (pintype "passive"))
      (node (ref "SJ7") (pin "P$2") (pinfunction "2_P$2") (pintype "passive"))
      (node (ref "SJ8") (pin "P$2") (pinfunction "2_P$2") (pintype "passive"))
      (node (ref "U1") (pin "3") (pinfunction "VCC_3") (pintype "power_in"))
      (node (ref "U11") (pin "10") (pinfunction "SCL_10") (pintype "input"))
      (node (ref "U11") (pin "16") (pinfunction "VCC_16") (pintype "power_in"))
      (node (ref "U13") (pin "10") (pinfunction "SCL_10") (pintype "input"))
      (node (ref "U13") (pin "16") (pinfunction "VCC_16") (pintype "power_in"))
      (node (ref "X5") (pin "1") (pinfunction "1_1") (pintype "passive"))
    )
    (net (code "3") (name "+12V") (class "Default")
      (node (ref "C10") (pin "1") (pinfunction "1_1") (pintype "passive"))
      (node (ref "C5") (pin "1") (pinfunction "1_1") (pintype "passive"))
      (node (ref "C9") (pin "1") (pinfunction "1_1") (pintype "passive"))
      (node (ref "D5") (pin "C") (pinfunction "C_C") (pintype "passive"))
      (node (ref "D6") (pin "C") (pinfunction "C_C") (pintype "passive"))
      (node (ref "IC1") (pin "5") (pinfunction "IN_5") (pintype "input"))
      (node (ref "JP5") (pin "7") (pinfunction "7_7") (pintype "passive"))
      (node (ref "JP7") (pin "2") (pinfunction "2_2") (pintype "passive"))
      (node (ref "SJ10") (pin "P$2") (pinfunction "2_P$2") (pintype "passive"))
      (node (ref "SJ16") (pin "P$2") (pinfunction "2_P$2") (pintype "passive"))
      (node (ref "SJ17") (pin "P$2") (pinfunction "2_P$2") (pintype "passive"))
      (node (ref "SJ2") (pin "P$2") (pinfunction "2_P$2") (pintype "passive"))
      (node (ref "SJ9") (pin "P$2") (pinfunction "2_P$2") (pintype "passive"))
      (node (ref "U10") (pin "6") (pinfunction "VDD_6") (pintype "power_in"))
      (node (ref "U2") (pin "1") (pinfunction "VIN_1") (pintype "bidirectional"))
      (node (ref "U5") (pin "6") (pinfunction "VDD_6") (pintype "power_in"))
      (node (ref "U6") (pin "4") (pinfunction "V+_4") (pintype "power_in"))
      (node (ref "U7") (pin "6") (pinfunction "VDD_6") (pintype "power_in"))
      (node (ref "U8") (pin "6") (pinfunction "VDD_6") (pintype "power_in"))
      (node (ref "U9") (pin "4") (pinfunction "V+_4") (pintype "power_in"))
    )
    (net (code "4") (name "/AGND") (class "Default")
      (node (ref "G1") (pin "AGND") (pinfunction "AGND_AGND") (pintype "power_in"))
    )
    (net (code "5") (name "/AVDD") (class "Default")
      (node (ref "G1") (pin "AVDD") (pinfunction "AVDD_AVDD") (pintype "power_in"))
    )
    (net (code "6") (name "/CANH") (class "Default")
      (node (ref "IC2") (pin "7") (pinfunction "CANH_7") (pintype "bidirectional"))
      (node (ref "U1") (pin "7") (pinfunction "CANH_7") (pintype "bidirectional"))
      (node (ref "X1") (pin "1") (pinfunction "1_1") (pintype "passive"))
      (node (ref "X2") (pin "1") (pinfunction "1_1") (pintype "passive"))
    )
    (net (code "7") (name "/CANL") (class "Default")
      (node (ref "IC2") (pin "6") (pinfunction "CANL_6") (pintype "bidirectional"))
      (node (ref "U1") (pin "6") (pinfunction "CANL_6") (pintype "bidirectional"))
      (node (ref "X1") (pin "2") (pinfunction "2_2") (pintype "passive"))
      (node (ref "X2") (pin "2") (pinfunction "2_2") (pintype "passive"))
    )
    (net (code "8") (name "/GND4") (class "Default")
      (node (ref "G1") (pin "GND4") (pinfunction "GND4_GND4") (pintype "power_in"))
    )
    (net (code "9") (name "/PWR_POS") (class "Default")
      (node (ref "R17") (pin "2") (pinfunction "2_2") (pintype "passive"))
      (node (ref "X1") (pin "8") (pinfunction "8_8") (pintype "passive"))
      (node (ref "X2") (pin "8") (pinfunction "8_8") (pintype "passive"))
    )
    (net (code "10") (name "/U5V") (class "Default")
      (node (ref "G1") (pin "U5V") (pinfunction "U5V_U5V") (pintype "power_in"))
    )
    (net (code "11") (name "/VBAT") (class "Default")
      (node (ref "G1") (pin "VBAT") (pinfunction "VBAT_VBAT") (pintype "power_in"))
    )
    (net (code "12") (name "/VDD") (class "Default")
      (node (ref "G1") (pin "VDD") (pinfunction "VDD_VDD") (pintype "power_in"))
    )
    (net (code "13") (name "CANRX") (class "Default")
      (node (ref "G1") (pin "PB8") (pinfunction "PB8_PB8") (pintype "bidirectional"))
      (node (ref "IC2") (pin "4") (pinfunction "RXD_4") (pintype "bidirectional"))
      (node (ref "U1") (pin "4") (pinfunction "RXD_4") (pintype "output"))
    )
    (net (code "14") (name "CANTX") (class "Default")
      (node (ref "G1") (pin "PB9") (pinfunction "PB9_PB9") (pintype "bidirectional"))
      (node (ref "IC2") (pin "1") (pinfunction "TXD_1") (pintype "bidirectional"))
      (node (ref "U1") (pin "1") (pinfunction "TXD_1") (pintype "input"))
    )
    (net (code "15") (name "E_CS") (class "Default")
      (node (ref "G1") (pin "PC10") (pinfunction "PC10_PC10") (pintype "bidirectional"))
      (node (ref "JP5") (pin "4") (pinfunction "4_4") (pintype "passive"))
      (node (ref "R1") (pin "2") (pinfunction "2_2") (pintype "passive"))
    )
    (net (code "16") (name "E_LAT") (class "Default")
      (node (ref "G1") (pin "PC11") (pinfunction "PC11_PC11") (pintype "bidirectional"))
      (node (ref "JP5") (pin "5") (pinfunction "5_5") (pintype "passive"))
      (node (ref "R2") (pin "2") (pinfunction "2_2") (pintype "passive"))
    )
    (net (code "17") (name "GND") (class "Default")
      (node (ref "C1") (pin "2") (pinfunction "2_2") (pintype "passive"))
      (node (ref "C10") (pin "2") (pinfunction "2_2") (pintype "passive"))
      (node (ref "C11") (pin "2") (pinfunction "2_2") (pintype "passive"))
      (node (ref "C2") (pin "2") (pinfunction "2_2") (pintype "passive"))
      (node (ref "C3") (pin "2") (pinfunction "2_2") (pintype "passive"))
      (node (ref "C4") (pin "2") (pinfunction "2_2") (pintype "passive"))
      (node (ref "C5") (pin "2") (pinfunction "2_2") (pintype "passive"))
      (node (ref "C6") (pin "-") (pinfunction "-_-") (pintype "passive"))
      (node (ref "C7") (pin "2") (pinfunction "2_2") (pintype "passive"))
      (node (ref "C8") (pin "2") (pinfunction "2_2") (pintype "passive"))
      (node (ref "C9") (pin "2") (pinfunction "2_2") (pintype "passive"))
      (node (ref "D3") (pin "A") (pinfunction "A_A") (pintype "passive"))
      (node (ref "D4") (pin "A") (pinfunction "A_A") (pintype "passive"))
      (node (ref "G1") (pin "GND3") (pinfunction "GND3_GND3") (pintype "power_in"))
      (node (ref "G1") (pin "GND5") (pinfunction "GND5_GND5") (pintype "power_in"))
      (node (ref "G1") (pin "GND6") (pinfunction "GND6_GND6") (pintype "power_in"))
      (node (ref "G1") (pin "GND7") (pinfunction "GND7_GND7") (pintype "power_in"))
      (node (ref "G1") (pin "GND8") (pinfunction "GND8_GND8") (pintype "power_in"))
      (node (ref "IC1") (pin "2") (pinfunction "GNDSIG_2") (pintype "input"))
      (node (ref "IC1") (pin "3") (pinfunction "~{ON/OFF}_3") (pintype "input"))
      (node (ref "IC1") (pin "4") (pinfunction "GND_4") (pintype "power_in"))
      (node (ref "IC2") (pin "2") (pinfunction "VSS_2") (pintype "power_in"))
      (node (ref "J1") (pin "2") (pinfunction "2_2") (pintype "passive"))
      (node (ref "J1") (pin "3") (pinfunction "3_3") (pintype "passive"))
      (node (ref "JP1") (pin "5") (pinfunction "5_5") (pintype "passive"))
      (node (ref "JP1") (pin "6") (pinfunction "6_6") (pintype "passive"))
      (node (ref "JP10") (pin "5") (pinfunction "5_5") (pintype "passive"))
      (node (ref "JP2") (pin "5") (pinfunction "5_5") (pintype "passive"))
      (node (ref "JP2") (pin "6") (pinfunction "6_6") (pintype "passive"))
      (node (ref "JP3") (pin "5") (pinfunction "5_5") (pintype "passive"))
      (node (ref "JP3") (pin "6") (pinfunction "6_6") (pintype "passive"))
      (node (ref "JP4") (pin "5") (pinfunction "5_5") (pintype "passive"))
      (node (ref "JP4") (pin "6") (pinfunction "6_6") (pintype "passive"))
      (node (ref "JP5") (pin "8") (pinfunction "8_8") (pintype "passive"))
      (node (ref "JP6") (pin "4") (pinfunction "4_4") (pintype "passive"))
      (node (ref "JP8") (pin "5") (pinfunction "5_5") (pintype "passive"))
      (node (ref "JP9") (pin "5") (pinfunction "5_5") (pintype "passive"))
      (node (ref "Q1") (pin "2") (pinfunction "S_2") (pintype "passive"))
      (node (ref "Q10") (pin "2") (pinfunction "S_2") (pintype "passive"))
      (node (ref "Q11") (pin "2") (pinfunction "S_2") (pintype "passive"))
      (node (ref "Q12") (pin "2") (pinfunction "S_2") (pintype "passive"))
      (node (ref "Q13") (pin "2") (pinfunction "S_2") (pintype "passive"))
      (node (ref "Q14") (pin "2") (pinfunction "S_2") (pintype "passive"))
      (node (ref "Q15") (pin "2") (pinfunction "S_2") (pintype "passive"))
      (node (ref "Q16") (pin "2") (pinfunction "S_2") (pintype "passive"))
      (node (ref "Q2") (pin "2") (pinfunction "S_2") (pintype "passive"))
      (node (ref "Q3") (pin "2") (pinfunction "S_2") (pintype "passive"))
      (node (ref "Q4") (pin "2") (pinfunction "S_2") (pintype "passive"))
      (node (ref "Q5") (pin "2") (pinfunction "S_2") (pintype "passive"))
      (node (ref "Q6") (pin "2") (pinfunction "S_2") (pintype "passive"))
      (node (ref "Q7") (pin "2") (pinfunction "S_2") (pintype "passive"))
      (node (ref "Q8") (pin "2") (pinfunction "S_2") (pintype "passive"))
      (node (ref "Q9") (pin "2") (pinfunction "S_2") (pintype "passive"))
      (node (ref "R16") (pin "2") (pinfunction "2_2") (pintype "passive"))
      (node (ref "R51") (pin "1") (pinfunction "1_1") (pintype "passive"))
      (node (ref "SJ11") (pin "2") (pinfunction "2_2") (pintype "passive"))
      (node (ref "SJ12") (pin "P$2") (pinfunction "2_P$2") (pintype "passive"))
      (node (ref "SJ18") (pin "2") (pinfunction "2_2") (pintype "passive"))
      (node (ref "SJ19") (pin "P$2") (pinfunction "2_P$2") (pintype "passive"))
      (node (ref "U1") (pin "2") (pinfunction "GND_2") (pintype "power_in"))
      (node (ref "U10") (pin "3") (pinfunction "VSS_3") (pintype "power_in"))
      (node (ref "U11") (pin "13") (pinfunction "G_13") (pintype "input"))
      (node (ref "U11") (pin "8") (pinfunction "GND_8") (pintype "power_in"))
      (node (ref "U13") (pin "13") (pinfunction "G_13") (pintype "input"))
      (node (ref "U13") (pin "8") (pinfunction "GND_8") (pintype "power_in"))
      (node (ref "U2") (pin "4") (pinfunction "SD_4") (pintype "bidirectional"))
      (node (ref "U2") (pin "5") (pinfunction "GND1_5") (pintype "power_in"))
      (node (ref "U2") (pin "6") (pinfunction "GND2_6") (pintype "power_in"))
      (node (ref "U2") (pin "7") (pinfunction "GND3_7") (pintype "power_in"))
      (node (ref "U2") (pin "8") (pinfunction "GND4_8") (pintype "power_in"))
      (node (ref "U3") (pin "6") (pinfunction "INH_6") (pintype "input"))
      (node (ref "U3") (pin "8") (pinfunction "GND_8") (pintype "power_in"))
      (node (ref "U4") (pin "6") (pinfunction "INH_6") (pintype "input"))
      (node (ref "U4") (pin "8") (pinfunction "GND_8") (pintype "power_in"))
      (node (ref "U5") (pin "3") (pinfunction "VSS_3") (pintype "power_in"))
      (node (ref "U6") (pin "11") (pinfunction "V-_11") (pintype "power_in"))
      (node (ref "U7") (pin "3") (pinfunction "VSS_3") (pintype "power_in"))
      (node (ref "U8") (pin "3") (pinfunction "VSS_3") (pintype "power_in"))
      (node (ref "U9") (pin "11") (pinfunction "V-_11") (pintype "power_in"))
      (node (ref "X1") (pin "3") (pinfunction "3_3") (pintype "passive"))
      (node (ref "X1") (pin "6") (pinfunction "6_6") (pintype "passive"))
      (node (ref "X1") (pin "7") (pinfunction "7_7") (pintype "passive"))
      (node (ref "X2") (pin "3") (pinfunction "3_3") (pintype "passive"))
      (node (ref "X2") (pin "6") (pinfunction "6_6") (pintype "passive"))
      (node (ref "X2") (pin "7") (pinfunction "7_7") (pintype "passive"))
      (node (ref "X5") (pin "2") (pinfunction "2_2") (pintype "passive"))
      (node (ref "X9") (pin "2") (pinfunction "2_2") (pintype "passive"))
    )
    (net (code "18") (name "I2CSCL") (class "Default")
      (node (ref "G1") (pin "PB6") (pinfunction "PB6_PB6") (pintype "bidirectional"))
      (node (ref "JP6") (pin "1") (pinfunction "1_1") (pintype "passive"))
      (node (ref "R15") (pin "2") (pinfunction "2_2") (pintype "passive"))
    )
    (net (code "19") (name "I2CSDA") (class "Default")
      (node (ref "G1") (pin "PB7") (pinfunction "PB7_PB7") (pintype "bidirectional"))
      (node (ref "JP6") (pin "2") (pinfunction "2_2") (pintype "passive"))
      (node (ref "R14") (pin "2") (pinfunction "2_2") (pintype "passive"))
    )
    (net (code "20") (name "ILAT") (class "Default")
      (node (ref "G1") (pin "PA6") (pinfunction "PA6_PA6") (pintype "bidirectional"))
      (node (ref "U3") (pin "15") (pinfunction "SH/~{LD}_15") (pintype "input"))
      (node (ref "U4") (pin "15") (pinfunction "SH/~{LD}_15") (pintype "input"))
    )
    (net (code "21") (name "MISO") (class "Default")
      (node (ref "G1") (pin "PB4") (pinfunction "PB4_PB4") (pintype "bidirectional"))
      (node (ref "JP5") (pin "1") (pinfunction "1_1") (pintype "passive"))
    )
    (net (code "22") (name "MISO2") (class "Default")
      (node (ref "G1") (pin "PC2") (pinfunction "PC2_PC2") (pintype "bidirectional"))
      (node (ref "SJ1") (pin "P$2") (pinfunction "2_P$2") (pintype "passive"))
      (node (ref "SJ6") (pin "P$2") (pinfunction "2_P$2") (pintype "passive"))
      (node (ref "U3") (pin "13") (pinfunction "QH_13") (pintype "output"))
    )
    (net (code "23") (name "MOSI") (class "Default")
      (node (ref "G1") (pin "PB5") (pinfunction "PB5_PB5") (pintype "bidirectional"))
      (node (ref "R4") (pin "1") (pinfunction "1_1") (pintype "passive"))
      (node (ref "SJ13") (pin "P$2") (pinfunction "2_P$2") (pintype "passive"))
      (node (ref "SJ3") (pin "1") (pinfunction "1_1") (pintype "passive"))
      (node (ref "U13") (pin "14") (pinfunction "SER_14") (pintype "input"))
    )
    (net (code "24") (name "Net-(D1-PadA)") (class "Default")
      (node (ref "D1") (pin "A") (pinfunction "A_A") (pintype "passive"))
      (node (ref "D2") (pin "A") (pinfunction "A_A") (pintype "passive"))
      (node (ref "JP7") (pin "4") (pinfunction "4_4") (pintype "passive"))
    )
    (net (code "25") (name "Net-(D1-PadC)") (class "Default")
      (node (ref "D1") (pin "C") (pinfunction "C_C") (pintype "passive"))
      (node (ref "D2") (pin "C") (pinfunction "C_C") (pintype "passive"))
      (node (ref "JP7") (pin "1") (pinfunction "1_1") (pintype "passive"))
    )
    (net (code "26") (name "Net-(D5-PadA)") (class "Default")
      (node (ref "D5") (pin "A") (pinfunction "A_A") (pintype "passive"))
      (node (ref "D6") (pin "A") (pinfunction "A_A") (pintype "passive"))
      (node (ref "J1") (pin "1") (pinfunction "1_1") (pintype "passive"))
      (node (ref "X9") (pin "1") (pinfunction "1_1") (pintype "passive"))
    )
    (net (code "27") (name "Net-(IC1-OUT)") (class "Default")
      (node (ref "D3") (pin "C") (pinfunction "C_C") (pintype "passive"))
      (node (ref "D4") (pin "C") (pinfunction "C_C") (pintype "passive"))
      (node (ref "IC1") (pin "7") (pinfunction "OUT_7") (pintype "passive"))
      (node (ref "L1") (pin "2") (pinfunction "2_2") (pintype "passive"))
      (node (ref "U2") (pin "2") (pinfunction "VOUT_2") (pintype "bidirectional"))
    )
    (net (code "28") (name "Net-(IC2-RS)") (class "Default")
      (node (ref "IC2") (pin "8") (pinfunction "RS_8") (pintype "bidirectional"))
      (node (ref "R16") (pin "1") (pinfunction "1_1") (pintype "passive"))
      (node (ref "U1") (pin "8") (pinfunction "RS_8") (pintype "input"))
    )
    (net (code "29") (name "Net-(IC2-VREF)") (class "Default")
      (node (ref "IC2") (pin "5") (pinfunction "VREF_5") (pintype "bidirectional"))
      (node (ref "SJ5") (pin "P$2") (pinfunction "2_P$2") (pintype "passive"))
      (node (ref "U1") (pin "5") (pinfunction "VREF_5") (pintype "output"))
    )
    (net (code "30") (name "Net-(JP7-Pad3)") (class "Default")
      (node (ref "JP7") (pin "3") (pinfunction "3_3") (pintype "passive"))
      (node (ref "R17") (pin "1") (pinfunction "1_1") (pintype "passive"))
    )
    (net (code "31") (name "Net-(JP8-Pad1)") (class "Default")
      (node (ref "JP8") (pin "1") (pinfunction "1_1") (pintype "passive"))
      (node (ref "R25") (pin "2") (pinfunction "2_2") (pintype "passive"))
      (node (ref "R26") (pin "2") (pinfunction "2_2") (pintype "passive"))
      (node (ref "RN1") (pin "9") (pinfunction "9_9") (pintype "passive"))
      (node (ref "RN2") (pin "1") (pinfunction "1_1") (pintype "passive"))
      (node (ref "X3") (pin "1") (pinfunction "1_1") (pintype "passive"))
    )
    (net (code "32") (name "Net-(JP9-Pad1)") (class "Default")
      (node (ref "JP9") (pin "1") (pinfunction "1_1") (pintype "passive"))
      (node (ref "R41") (pin "2") (pinfunction "2_2") (pintype "passive"))
      (node (ref "R42") (pin "2") (pinfunction "2_2") (pintype "passive"))
      (node (ref "RN3") (pin "9") (pinfunction "9_9") (pintype "passive"))
      (node (ref "RN4") (pin "1") (pinfunction "1_1") (pintype "passive"))
      (node (ref "X4") (pin "1") (pinfunction "1_1") (pintype "passive"))
    )
    (net (code "33") (name "Net-(Q1-D)") (class "Default")
      (node (ref "Q1") (pin "3") (pinfunction "D_3") (pintype "passive"))
      (node (ref "U12") (pin "11") (pinfunction "O8_11") (pintype "open_collector"))
      (node (ref "X7") (pin "8") (pinfunction "8_8") (pintype "passive"))
    )
    (net (code "34") (name "Net-(Q1-G)") (class "Default")
      (node (ref "Q1") (pin "1") (pinfunction "G_1") (pintype "passive"))
      (node (ref "R52") (pin "2") (pinfunction "2_2") (pintype "passive"))
    )
    (net (code "35") (name "Net-(Q2-D)") (class "Default")
      (node (ref "Q2") (pin "3") (pinfunction "D_3") (pintype "passive"))
      (node (ref "U12") (pin "12") (pinfunction "O7_12") (pintype "open_collector"))
      (node (ref "X7") (pin "7") (pinfunction "7_7") (pintype "passive"))
    )
    (net (code "36") (name "Net-(Q2-G)") (class "Default")
      (node (ref "Q2") (pin "1") (pinfunction "G_1") (pintype "passive"))
      (node (ref "R53") (pin "2") (pinfunction "2_2") (pintype "passive"))
    )
    (net (code "37") (name "Net-(Q3-D)") (class "Default")
      (node (ref "Q3") (pin "3") (pinfunction "D_3") (pintype "passive"))
      (node (ref "U12") (pin "13") (pinfunction "O6_13") (pintype "open_collector"))
      (node (ref "X7") (pin "6") (pinfunction "6_6") (pintype "passive"))
    )
    (net (code "38") (name "Net-(Q3-G)") (class "Default")
      (node (ref "Q3") (pin "1") (pinfunction "G_1") (pintype "passive"))
      (node (ref "R54") (pin "2") (pinfunction "2_2") (pintype "passive"))
    )
    (net (code "39") (name "Net-(Q4-D)") (class "Default")
      (node (ref "Q4") (pin "3") (pinfunction "D_3") (pintype "passive"))
      (node (ref "U12") (pin "14") (pinfunction "O5_14") (pintype "open_collector"))
      (node (ref "X7") (pin "5") (pinfunction "5_5") (pintype "passive"))
    )
    (net (code "40") (name "Net-(Q4-G)") (class "Default")
      (node (ref "Q4") (pin "1") (pinfunction "G_1") (pintype "passive"))
      (node (ref "R55") (pin "2") (pinfunction "2_2") (pintype "passive"))
    )
    (net (code "41") (name "Net-(Q5-D)") (class "Default")
      (node (ref "Q5") (pin "3") (pinfunction "D_3") (pintype "passive"))
      (node (ref "U12") (pin "15") (pinfunction "O4_15") (pintype "open_collector"))
      (node (ref "X7") (pin "4") (pinfunction "4_4") (pintype "passive"))
    )
    (net (code "42") (name "Net-(Q5-G)") (class "Default")
      (node (ref "Q5") (pin "1") (pinfunction "G_1") (pintype "passive"))
      (node (ref "R56") (pin "2") (pinfunction "2_2") (pintype "passive"))
    )
    (net (code "43") (name "Net-(Q6-D)") (class "Default")
      (node (ref "Q6") (pin "3") (pinfunction "D_3") (pintype "passive"))
      (node (ref "U12") (pin "16") (pinfunction "O3_16") (pintype "open_collector"))
      (node (ref "X7") (pin "3") (pinfunction "3_3") (pintype "passive"))
    )
    (net (code "44") (name "Net-(Q6-G)") (class "Default")
      (node (ref "Q6") (pin "1") (pinfunction "G_1") (pintype "passive"))
      (node (ref "R57") (pin "2") (pinfunction "2_2") (pintype "passive"))
    )
    (net (code "45") (name "Net-(Q7-D)") (class "Default")
      (node (ref "Q7") (pin "3") (pinfunction "D_3") (pintype "passive"))
      (node (ref "U12") (pin "17") (pinfunction "O2_17") (pintype "open_collector"))
      (node (ref "X7") (pin "2") (pinfunction "2_2") (pintype "passive"))
    )
    (net (code "46") (name "Net-(Q7-G)") (class "Default")
      (node (ref "Q7") (pin "1") (pinfunction "G_1") (pintype "passive"))
      (node (ref "R58") (pin "2") (pinfunction "2_2") (pintype "passive"))
    )
    (net (code "47") (name "Net-(Q8-D)") (class "Default")
      (node (ref "Q8") (pin "3") (pinfunction "D_3") (pintype "passive"))
      (node (ref "U12") (pin "18") (pinfunction "O1_18") (pintype "open_collector"))
      (node (ref "X7") (pin "1") (pinfunction "1_1") (pintype "passive"))
    )
    (net (code "48") (name "Net-(Q8-G)") (class "Default")
      (node (ref "Q8") (pin "1") (pinfunction "G_1") (pintype "passive"))
      (node (ref "R59") (pin "2") (pinfunction "2_2") (pintype "passive"))
    )
    (net (code "49") (name "Net-(Q9-D)") (class "Default")
      (node (ref "Q9") (pin "3") (pinfunction "D_3") (pintype "passive"))
      (node (ref "U14") (pin "11") (pinfunction "O8_11") (pintype "open_collector"))
      (node (ref "X8") (pin "8") (pinfunction "8_8") (pintype "passive"))
    )
    (net (code "50") (name "Net-(Q9-G)") (class "Default")
      (node (ref "Q9") (pin "1") (pinfunction "G_1") (pintype "passive"))
      (node (ref "R60") (pin "2") (pinfunction "2_2") (pintype "passive"))
    )
    (net (code "51") (name "Net-(Q10-D)") (class "Default")
      (node (ref "Q10") (pin "3") (pinfunction "D_3") (pintype "passive"))
      (node (ref "U14") (pin "12") (pinfunction "O7_12") (pintype "open_collector"))
      (node (ref "X8") (pin "7") (pinfunction "7_7") (pintype "passive"))
    )
    (net (code "52") (name "Net-(Q10-G)") (class "Default")
      (node (ref "Q10") (pin "1") (pinfunction "G_1") (pintype "passive"))
      (node (ref "R61") (pin "2") (pinfunction "2_2") (pintype "passive"))
    )
    (net (code "53") (name "Net-(Q11-D)") (class "Default")
      (node (ref "Q11") (pin "3") (pinfunction "D_3") (pintype "passive"))
      (node (ref "U14") (pin "13") (pinfunction "O6_13") (pintype "open_collector"))
      (node (ref "X8") (pin "6") (pinfunction "6_6") (pintype "passive"))
    )
    (net (code "54") (name "Net-(Q11-G)") (class "Default")
      (node (ref "Q11") (pin "1") (pinfunction "G_1") (pintype "passive"))
      (node (ref "R62") (pin "2") (pinfunction "2_2") (pintype "passive"))
    )
    (net (code "55") (name "Net-(Q12-D)") (class "Default")
      (node (ref "Q12") (pin "3") (pinfunction "D_3") (pintype "passive"))
      (node (ref "U14") (pin "14") (pinfunction "O5_14") (pintype "open_collector"))
      (node (ref "X8") (pin "5") (pinfunction "5_5") (pintype "passive"))
    )
    (net (code "56") (name "Net-(Q12-G)") (class "Default")
      (node (ref "Q12") (pin "1") (pinfunction "G_1") (pintype "passive"))
      (node (ref "R63") (pin "2") (pinfunction "2_2") (pintype "passive"))
    )
    (net (code "57") (name "Net-(Q13-D)") (class "Default")
      (node (ref "Q13") (pin "3") (pinfunction "D_3") (pintype "passive"))
      (node (ref "U14") (pin "15") (pinfunction "O4_15") (pintype "open_collector"))
      (node (ref "X8") (pin "4") (pinfunction "4_4") (pintype "passive"))
    )
    (net (code "58") (name "Net-(Q13-G)") (class "Default")
      (node (ref "Q13") (pin "1") (pinfunction "G_1") (pintype "passive"))
      (node (ref "R64") (pin "2") (pinfunction "2_2") (pintype "passive"))
    )
    (net (code "59") (name "Net-(Q14-D)") (class "Default")
      (node (ref "Q14") (pin "3") (pinfunction "D_3") (pintype "passive"))
      (node (ref "U14") (pin "16") (pinfunction "O3_16") (pintype "open_collector"))
      (node (ref "X8") (pin "3") (pinfunction "3_3") (pintype "passive"))
    )
    (net (code "60") (name "Net-(Q14-G)") (class "Default")
      (node (ref "Q14") (pin "1") (pinfunction "G_1") (pintype "passive"))
      (node (ref "R65") (pin "2") (pinfunction "2_2") (pintype "passive"))
    )
    (net (code "61") (name "Net-(Q15-D)") (class "Default")
      (node (ref "Q15") (pin "3") (pinfunction "D_3") (pintype "passive"))
      (node (ref "U14") (pin "17") (pinfunction "O2_17") (pintype "open_collector"))
      (node (ref "X8") (pin "2") (pinfunction "2_2") (pintype "passive"))
    )
    (net (code "62") (name "Net-(Q15-G)") (class "Default")
      (node (ref "Q15") (pin "1") (pinfunction "G_1") (pintype "passive"))
      (node (ref "R66") (pin "2") (pinfunction "2_2") (pintype "passive"))
    )
    (net (code "63") (name "Net-(Q16-D)") (class "Default")
      (node (ref "Q16") (pin "3") (pinfunction "D_3") (pintype "passive"))
      (node (ref "U14") (pin "18") (pinfunction "O1_18") (pintype "open_collector"))
      (node (ref "X8") (pin "1") (pinfunction "1_1") (pintype "passive"))
    )
    (net (code "64") (name "Net-(Q16-G)") (class "Default")
      (node (ref "Q16") (pin "1") (pinfunction "G_1") (pintype "passive"))
      (node (ref "R67") (pin "2") (pinfunction "2_2") (pintype "passive"))
    )
    (net (code "65") (name "Net-(RN2A-2)") (class "Default")
      (node (ref "R25") (pin "1") (pinfunction "1_1") (pintype "passive"))
      (node (ref "RN2") (pin "16") (pinfunction "2_16") (pintype "passive"))
      (node (ref "U3") (pin "14") (pinfunction "H_14") (pintype "input"))
    )
    (net (code "66") (name "Net-(RN2B-1)") (class "Default")
      (node (ref "JP8") (pin "2") (pinfunction "2_2") (pintype "passive"))
      (node (ref "R24") (pin "2") (pinfunction "2_2") (pintype "passive"))
      (node (ref "R27") (pin "2") (pinfunction "2_2") (pintype "passive"))
      (node (ref "RN1") (pin "8") (pinfunction "8_8") (pintype "passive"))
      (node (ref "RN2") (pin "2") (pinfunction "1_2") (pintype "passive"))
      (node (ref "X3") (pin "2") (pinfunction "2_2") (pintype "passive"))
    )
    (net (code "67") (name "Net-(RN2B-2)") (class "Default")
      (node (ref "R24") (pin "1") (pinfunction "1_1") (pintype "passive"))
      (node (ref "RN2") (pin "15") (pinfunction "2_15") (pintype "passive"))
      (node (ref "U3") (pin "12") (pinfunction "G_12") (pintype "input"))
    )
    (net (code "68") (name "Net-(RN2C-1)") (class "Default")
      (node (ref "JP8") (pin "3") (pinfunction "3_3") (pintype "passive"))
      (node (ref "R23") (pin "2") (pinfunction "2_2") (pintype "passive"))
      (node (ref "R28") (pin "2") (pinfunction "2_2") (pintype "passive"))
      (node (ref "RN1") (pin "7") (pinfunction "7_7") (pintype "passive"))
      (node (ref "RN2") (pin "3") (pinfunction "1_3") (pintype "passive"))
      (node (ref "X3") (pin "3") (pinfunction "3_3") (pintype "passive"))
    )
    (net (code "69") (name "Net-(RN2C-2)") (class "Default")
      (node (ref "R23") (pin "1") (pinfunction "1_1") (pintype "passive"))
      (node (ref "RN2") (pin "14") (pinfunction "2_14") (pintype "passive"))
      (node (ref "U3") (pin "11") (pinfunction "F_11") (pintype "input"))
    )
    (net (code "70") (name "Net-(RN2D-1)") (class "Default")
      (node (ref "JP8") (pin "4") (pinfunction "4_4") (pintype "passive"))
      (node (ref "R22") (pin "2") (pinfunction "2_2") (pintype "passive"))
      (node (ref "R29") (pin "2") (pinfunction "2_2") (pintype "passive"))
      (node (ref "RN1") (pin "6") (pinfunction "6_6") (pintype "passive"))
      (node (ref "RN2") (pin "4") (pinfunction "1_4") (pintype "passive"))
      (node (ref "X3") (pin "4") (pinfunction "4_4") (pintype "passive"))
    )
    (net (code "71") (name "Net-(RN2D-2)") (class "Default")
      (node (ref "R22") (pin "1") (pinfunction "1_1") (pintype "passive"))
      (node (ref "RN2") (pin "13") (pinfunction "2_13") (pintype "passive"))
      (node (ref "U3") (pin "10") (pinfunction "E_10") (pintype "input"))
    )
    (net (code "72") (name "Net-(RN2E-1)") (class "Default")
      (node (ref "JP8") (pin "7") (pinfunction "7_7") (pintype "passive"))
      (node (ref "R21") (pin "2") (pinfunction "2_2") (pintype "passive"))
      (node (ref "R30") (pin "2") (pinfunction "2_2") (pintype "passive"))
      (node (ref "RN1") (pin "5") (pinfunction "5_5") (pintype "passive"))
      (node (ref "RN2") (pin "5") (pinfunction "1_5") (pintype "passive"))
      (node (ref "X3") (pin "5") (pinfunction "5_5") (pintype "passive"))
    )
    (net (code "73") (name "Net-(RN2E-2)") (class "Default")
      (node (ref "R21") (pin "1") (pinfunction "1_1") (pintype "passive"))
      (node (ref "RN2") (pin "12") (pinfunction "2_12") (pintype "passive"))
      (node (ref "U3") (pin "5") (pinfunction "D_5") (pintype "input"))
    )
    (net (code "74") (name "Net-(RN2F-1)") (class "Default")
      (node (ref "JP8") (pin "8") (pinfunction "8_8") (pintype "passive"))
      (node (ref "R20") (pin "2") (pinfunction "2_2") (pintype "passive"))
      (node (ref "R31") (pin "2") (pinfunction "2_2") (pintype "passive"))
      (node (ref "RN1") (pin "4") (pinfunction "4_4") (pintype "passive"))
      (node (ref "RN2") (pin "6") (pinfunction "1_6") (pintype "passive"))
      (node (ref "X3") (pin "6") (pinfunction "6_6") (pintype "passive"))
    )
    (net (code "75") (name "Net-(RN2F-2)") (class "Default")
      (node (ref "R20") (pin "1") (pinfunction "1_1") (pintype "passive"))
      (node (ref "RN2") (pin "11") (pinfunction "2_11") (pintype "passive"))
      (node (ref "U3") (pin "4") (pinfunction "C_4") (pintype "input"))
    )
    (net (code "76") (name "Net-(RN2G-1)") (class "Default")
      (node (ref "JP8") (pin "9") (pinfunction "9_9") (pintype "passive"))
      (node (ref "R19") (pin "2") (pinfunction "2_2") (pintype "passive"))
      (node (ref "R32") (pin "2") (pinfunction "2_2") (pintype "passive"))
      (node (ref "RN1") (pin "3") (pinfunction "3_3") (pintype "passive"))
      (node (ref "RN2") (pin "7") (pinfunction "1_7") (pintype "passive"))
      (node (ref "X3") (pin "7") (pinfunction "7_7") (pintype "passive"))
    )
    (net (code "77") (name "Net-(RN2G-2)") (class "Default")
      (node (ref "R19") (pin "1") (pinfunction "1_1") (pintype "passive"))
      (node (ref "RN2") (pin "10") (pinfunction "2_10") (pintype "passive"))
      (node (ref "U3") (pin "3") (pinfunction "B_3") (pintype "input"))
    )
    (net (code "78") (name "Net-(RN2H-1)") (class "Default")
      (node (ref "JP8") (pin "10") (pinfunction "10_10") (pintype "passive"))
      (node (ref "R18") (pin "2") (pinfunction "2_2") (pintype "passive"))
      (node (ref "R33") (pin "2") (pinfunction "2_2") (pintype "passive"))
      (node (ref "RN1") (pin "2") (pinfunction "2_2") (pintype "passive"))
      (node (ref "RN2") (pin "8") (pinfunction "1_8") (pintype "passive"))
      (node (ref "X3") (pin "8") (pinfunction "8_8") (pintype "passive"))
    )
    (net (code "79") (name "Net-(RN2H-2)") (class "Default")
      (node (ref "R18") (pin "1") (pinfunction "1_1") (pintype "passive"))
      (node (ref "RN2") (pin "9") (pinfunction "2_9") (pintype "passive"))
      (node (ref "U3") (pin "2") (pinfunction "A_2") (pintype "input"))
    )
    (net (code "80") (name "Net-(RN4A-2)") (class "Default")
      (node (ref "R41") (pin "1") (pinfunction "1_1") (pintype "passive"))
      (node (ref "RN4") (pin "16") (pinfunction "2_16") (pintype "passive"))
      (node (ref "U4") (pin "14") (pinfunction "H_14") (pintype "input"))
    )
    (net (code "81") (name "Net-(RN4B-1)") (class "Default")
      (node (ref "JP9") (pin "2") (pinfunction "2_2") (pintype "passive"))
      (node (ref "R40") (pin "2") (pinfunction "2_2") (pintype "passive"))
      (node (ref "R43") (pin "2") (pinfunction "2_2") (pintype "passive"))
      (node (ref "RN3") (pin "8") (pinfunction "8_8") (pintype "passive"))
      (node (ref "RN4") (pin "2") (pinfunction "1_2") (pintype "passive"))
      (node (ref "X4") (pin "2") (pinfunction "2_2") (pintype "passive"))
    )
    (net (code "82") (name "Net-(RN4B-2)") (class "Default")
      (node (ref "R40") (pin "1") (pinfunction "1_1") (pintype "passive"))
      (node (ref "RN4") (pin "15") (pinfunction "2_15") (pintype "passive"))
      (node (ref "U4") (pin "12") (pinfunction "G_12") (pintype "input"))
    )
    (net (code "83") (name "Net-(RN4C-1)") (class "Default")
      (node (ref "JP9") (pin "3") (pinfunction "3_3") (pintype "passive"))
      (node (ref "R39") (pin "2") (pinfunction "2_2") (pintype "passive"))
      (node (ref "R44") (pin "2") (pinfunction "2_2") (pintype "passive"))
      (node (ref "RN3") (pin "7") (pinfunction "7_7") (pintype "passive"))
      (node (ref "RN4") (pin "3") (pinfunction "1_3") (pintype "passive"))
      (node (ref "X4") (pin "3") (pinfunction "3_3") (pintype "passive"))
    )
    (net (code "84") (name "Net-(RN4C-2)") (class "Default")
      (node (ref "R39") (pin "1") (pinfunction "1_1") (pintype "passive"))
      (node (ref "RN4") (pin "14") (pinfunction "2_14") (pintype "passive"))
      (node (ref "U4") (pin "11") (pinfunction "F_11") (pintype "input"))
    )
    (net (code "85") (name "Net-(RN4D-1)") (class "Default")
      (node (ref "JP9") (pin "4") (pinfunction "4_4") (pintype "passive"))
      (node (ref "R38") (pin "2") (pinfunction "2_2") (pintype "passive"))
      (node (ref "R45") (pin "2") (pinfunction "2_2") (pintype "passive"))
      (node (ref "RN3") (pin "6") (pinfunction "6_6") (pintype "passive"))
      (node (ref "RN4") (pin "4") (pinfunction "1_4") (pintype "passive"))
      (node (ref "X4") (pin "4") (pinfunction "4_4") (pintype "passive"))
    )
    (net (code "86") (name "Net-(RN4D-2)") (class "Default")
      (node (ref "R38") (pin "1") (pinfunction "1_1") (pintype "passive"))
      (node (ref "RN4") (pin "13") (pinfunction "2_13") (pintype "passive"))
      (node (ref "U4") (pin "10") (pinfunction "E_10") (pintype "input"))
    )
    (net (code "87") (name "Net-(RN4E-1)") (class "Default")
      (node (ref "JP9") (pin "7") (pinfunction "7_7") (pintype "passive"))
      (node (ref "R37") (pin "2") (pinfunction "2_2") (pintype "passive"))
      (node (ref "R46") (pin "2") (pinfunction "2_2") (pintype "passive"))
      (node (ref "RN3") (pin "5") (pinfunction "5_5") (pintype "passive"))
      (node (ref "RN4") (pin "5") (pinfunction "1_5") (pintype "passive"))
      (node (ref "X4") (pin "5") (pinfunction "5_5") (pintype "passive"))
    )
    (net (code "88") (name "Net-(RN4E-2)") (class "Default")
      (node (ref "R37") (pin "1") (pinfunction "1_1") (pintype "passive"))
      (node (ref "RN4") (pin "12") (pinfunction "2_12") (pintype "passive"))
      (node (ref "U4") (pin "5") (pinfunction "D_5") (pintype "input"))
    )
    (net (code "89") (name "Net-(RN4F-1)") (class "Default")
      (node (ref "JP9") (pin "8") (pinfunction "8_8") (pintype "passive"))
      (node (ref "R36") (pin "2") (pinfunction "2_2") (pintype "passive"))
      (node (ref "R47") (pin "2") (pinfunction "2_2") (pintype "passive"))
      (node (ref "RN3") (pin "4") (pinfunction "4_4") (pintype "passive"))
      (node (ref "RN4") (pin "6") (pinfunction "1_6") (pintype "passive"))
      (node (ref "X4") (pin "6") (pinfunction "6_6") (pintype "passive"))
    )
    (net (code "90") (name "Net-(RN4F-2)") (class "Default")
      (node (ref "R36") (pin "1") (pinfunction "1_1") (pintype "passive"))
      (node (ref "RN4") (pin "11") (pinfunction "2_11") (pintype "passive"))
      (node (ref "U4") (pin "4") (pinfunction "C_4") (pintype "input"))
    )
    (net (code "91") (name "Net-(RN4G-1)") (class "Default")
      (node (ref "JP9") (pin "9") (pinfunction "9_9") (pintype "passive"))
      (node (ref "R35") (pin "2") (pinfunction "2_2") (pintype "passive"))
      (node (ref "R48") (pin "2") (pinfunction "2_2") (pintype "passive"))
      (node (ref "RN3") (pin "3") (pinfunction "3_3") (pintype "passive"))
      (node (ref "RN4") (pin "7") (pinfunction "1_7") (pintype "passive"))
      (node (ref "X4") (pin "7") (pinfunction "7_7") (pintype "passive"))
    )
    (net (code "92") (name "Net-(RN4G-2)") (class "Default")
      (node (ref "R35") (pin "1") (pinfunction "1_1") (pintype "passive"))
      (node (ref "RN4") (pin "10") (pinfunction "2_10") (pintype "passive"))
      (node (ref "U4") (pin "3") (pinfunction "B_3") (pintype "input"))
    )
    (net (code "93") (name "Net-(RN4H-1)") (class "Default")
      (node (ref "JP9") (pin "10") (pinfunction "10_10") (pintype "passive"))
      (node (ref "R34") (pin "2") (pinfunction "2_2") (pintype "passive"))
      (node (ref "R49") (pin "2") (pinfunction "2_2") (pintype "passive"))
      (node (ref "RN3") (pin "2") (pinfunction "2_2") (pintype "passive"))
      (node (ref "RN4") (pin "8") (pinfunction "1_8") (pintype "passive"))
      (node (ref "X4") (pin "8") (pinfunction "8_8") (pintype "passive"))
    )
    (net (code "94") (name "Net-(RN4H-2)") (class "Default")
      (node (ref "R34") (pin "1") (pinfunction "1_1") (pintype "passive"))
      (node (ref "RN4") (pin "9") (pinfunction "2_9") (pintype "passive"))
      (node (ref "U4") (pin "2") (pinfunction "A_2") (pintype "input"))
    )
    (net (code "95") (name "Net-(SJ1-1)") (class "Default")
      (node (ref "G1") (pin "PB14") (pinfunction "PB14_PB14") (pintype "bidirectional"))
      (node (ref "SJ1") (pin "P$1") (pinfunction "1_P$1") (pintype "passive"))
    )
    (net (code "96") (name "Net-(SJ2-1)") (class "Default")
      (node (ref "G1") (pin "VIN2") (pinfunction "VIN2_VIN2") (pintype "power_in"))
      (node (ref "SJ2") (pin "P$1") (pinfunction "1_P$1") (pintype "passive"))
    )
    (net (code "97") (name "Net-(SJ4-2)") (class "Default")
      (node (ref "JP5") (pin "2") (pinfunction "2_2") (pintype "passive"))
      (node (ref "SJ3") (pin "2") (pinfunction "2_2") (pintype "passive"))
      (node (ref "SJ4") (pin "P$2") (pinfunction "2_P$2") (pintype "passive"))
    )
    (net (code "98") (name "Net-(SJ7-1)") (class "Default")
      (node (ref "SJ11") (pin "1") (pinfunction "1_1") (pintype "passive"))
      (node (ref "SJ7") (pin "P$1") (pinfunction "1_P$1") (pintype "passive"))
      (node (ref "SJ9") (pin "P$1") (pinfunction "1_P$1") (pintype "passive"))
      (node (ref "U12") (pin "9") (pinfunction "GND_9") (pintype "power_in"))
    )
    (net (code "99") (name "Net-(SJ10-1)") (class "Default")
      (node (ref "SJ10") (pin "P$1") (pinfunction "1_P$1") (pintype "passive"))
      (node (ref "SJ12") (pin "P$1") (pinfunction "1_P$1") (pintype "passive"))
      (node (ref "SJ8") (pin "P$1") (pinfunction "1_P$1") (pintype "passive"))
      (node (ref "U12") (pin "10") (pinfunction "CD+_10") (pintype "passive"))
      (node (ref "X7") (pin "9") (pinfunction "9_9") (pintype "passive"))
    )
    (net (code "100") (name "Net-(SJ14-1)") (class "Default")
      (node (ref "SJ14") (pin "P$1") (pinfunction "1_P$1") (pintype "passive"))
      (node (ref "SJ16") (pin "P$1") (pinfunction "1_P$1") (pintype "passive"))
      (node (ref "SJ18") (pin "1") (pinfunction "1_1") (pintype "passive"))
      (node (ref "U14") (pin "9") (pinfunction "GND_9") (pintype "power_in"))
    )
    (net (code "101") (name "Net-(SJ15-1)") (class "Default")
      (node (ref "SJ15") (pin "P$1") (pinfunction "1_P$1") (pintype "passive"))
      (node (ref "SJ17") (pin "P$1") (pinfunction "1_P$1") (pintype "passive"))
      (node (ref "SJ19") (pin "P$1") (pinfunction "1_P$1") (pintype "passive"))
      (node (ref "U14") (pin "10") (pinfunction "CD+_10") (pintype "passive"))
      (node (ref "X8") (pin "9") (pinfunction "9_9") (pintype "passive"))
    )
    (net (code "102") (name "Net-(SJ20-2)") (class "Default")
      (node (ref "G1") (pin "PB13") (pinfunction "PB13_PB13") (pintype "bidirectional"))
      (node (ref "SJ20") (pin "P$2") (pinfunction "2_P$2") (pintype "passive"))
    )
    (net (code "103") (name "Net-(U5A-O)") (class "Default")
      (node (ref "JP10") (pin "1") (pinfunction "1_1") (pintype "passive"))
      (node (ref "U5") (pin "7") (pinfunction "O_7") (pintype "output"))
      (node (ref "U6") (pin "7") (pinfunction "OUT_7") (pintype "output"))
      (node (ref "X6") (pin "1") (pinfunction "1_1") (pintype "passive"))
    )
    (net (code "104") (name "Net-(U5B-O)") (class "Default")
      (node (ref "JP10") (pin "2") (pinfunction "2_2") (pintype "passive"))
      (node (ref "U5") (pin "5") (pinfunction "O_5") (pintype "output"))
      (node (ref "U6") (pin "8") (pinfunction "OUT_8") (pintype "output"))
      (node (ref "X6") (pin "2") (pinfunction "2_2") (pintype "passive"))
    )
    (net (code "105") (name "Net-(U6A--IN)") (class "Default")
      (node (ref "R50") (pin "1") (pinfunction "1_1") (pintype "passive"))
      (node (ref "R51") (pin "2") (pinfunction "2_2") (pintype "passive"))
      (node (ref "U6") (pin "13") (pinfunction "-IN_13") (pintype "input"))
      (node (ref "U6") (pin "2") (pinfunction "-IN_2") (pintype "input"))
      (node (ref "U6") (pin "6") (pinfunction "-IN_6") (pintype "input"))
      (node (ref "U6") (pin "9") (pinfunction "-IN_9") (pintype "input"))
      (node (ref "U9") (pin "13") (pinfunction "-IN_13") (pintype "input"))
      (node (ref "U9") (pin "2") (pinfunction "-IN_2") (pintype "input"))
      (node (ref "U9") (pin "6") (pinfunction "-IN_6") (pintype "input"))
      (node (ref "U9") (pin "9") (pinfunction "-IN_9") (pintype "input"))
    )
    (net (code "106") (name "Net-(U6A-OUT)") (class "Default")
      (node (ref "JP10") (pin "3") (pinfunction "3_3") (pintype "passive"))
      (node (ref "U6") (pin "1") (pinfunction "OUT_1") (pintype "output"))
      (node (ref "U7") (pin "5") (pinfunction "O_5") (pintype "output"))
      (node (ref "X6") (pin "3") (pinfunction "3_3") (pintype "passive"))
    )
    (net (code "107") (name "Net-(U6D-OUT)") (class "Default")
      (node (ref "JP10") (pin "4") (pinfunction "4_4") (pintype "passive"))
      (node (ref "U6") (pin "14") (pinfunction "OUT_14") (pintype "output"))
      (node (ref "U7") (pin "7") (pinfunction "O_7") (pintype "output"))
      (node (ref "X6") (pin "4") (pinfunction "4_4") (pintype "passive"))
    )
    (net (code "108") (name "Net-(U8A-O)") (class "Default")
      (node (ref "JP10") (pin "7") (pinfunction "7_7") (pintype "passive"))
      (node (ref "U8") (pin "7") (pinfunction "O_7") (pintype "output"))
      (node (ref "U9") (pin "7") (pinfunction "OUT_7") (pintype "output"))
      (node (ref "X6") (pin "5") (pinfunction "5_5") (pintype "passive"))
    )
    (net (code "109") (name "Net-(U8B-O)") (class "Default")
      (node (ref "JP10") (pin "8") (pinfunction "8_8") (pintype "passive"))
      (node (ref "U8") (pin "5") (pinfunction "O_5") (pintype "output"))
      (node (ref "U9") (pin "8") (pinfunction "OUT_8") (pintype "output"))
      (node (ref "X6") (pin "6") (pinfunction "6_6") (pintype "passive"))
    )
    (net (code "110") (name "Net-(U10A-O)") (class "Default")
      (node (ref "JP10") (pin "10") (pinfunction "10_10") (pintype "passive"))
      (node (ref "U10") (pin "7") (pinfunction "O_7") (pintype "output"))
      (node (ref "U9") (pin "14") (pinfunction "OUT_14") (pintype "output"))
      (node (ref "X6") (pin "8") (pinfunction "8_8") (pintype "passive"))
    )
    (net (code "111") (name "Net-(U10B-O)") (class "Default")
      (node (ref "JP10") (pin "9") (pinfunction "9_9") (pintype "passive"))
      (node (ref "U10") (pin "5") (pinfunction "O_5") (pintype "output"))
      (node (ref "U9") (pin "1") (pinfunction "OUT_1") (pintype "output"))
      (node (ref "X6") (pin "7") (pinfunction "7_7") (pintype "passive"))
    )
    (net (code "112") (name "Net-(U11A-QA)") (class "Default")
      (node (ref "R59") (pin "1") (pinfunction "1_1") (pintype "passive"))
      (node (ref "U11") (pin "15") (pinfunction "QA_15") (pintype "tri_state"))
      (node (ref "U12") (pin "1") (pinfunction "I1_1") (pintype "input"))
    )
    (net (code "113") (name "Net-(U11A-QB)") (class "Default")
      (node (ref "R58") (pin "1") (pinfunction "1_1") (pintype "passive"))
      (node (ref "U11") (pin "1") (pinfunction "QB_1") (pintype "tri_state"))
      (node (ref "U12") (pin "2") (pinfunction "I2_2") (pintype "input"))
    )
    (net (code "114") (name "Net-(U11A-QC)") (class "Default")
      (node (ref "R57") (pin "1") (pinfunction "1_1") (pintype "passive"))
      (node (ref "U11") (pin "2") (pinfunction "QC_2") (pintype "tri_state"))
      (node (ref "U12") (pin "3") (pinfunction "I3_3") (pintype "input"))
    )
    (net (code "115") (name "Net-(U11A-QD)") (class "Default")
      (node (ref "R56") (pin "1") (pinfunction "1_1") (pintype "passive"))
      (node (ref "U11") (pin "3") (pinfunction "QD_3") (pintype "tri_state"))
      (node (ref "U12") (pin "4") (pinfunction "I4_4") (pintype "input"))
    )
    (net (code "116") (name "Net-(U11A-QE)") (class "Default")
      (node (ref "R55") (pin "1") (pinfunction "1_1") (pintype "passive"))
      (node (ref "U11") (pin "4") (pinfunction "QE_4") (pintype "tri_state"))
      (node (ref "U12") (pin "5") (pinfunction "I5_5") (pintype "input"))
    )
    (net (code "117") (name "Net-(U11A-QF)") (class "Default")
      (node (ref "R54") (pin "1") (pinfunction "1_1") (pintype "passive"))
      (node (ref "U11") (pin "5") (pinfunction "QF_5") (pintype "tri_state"))
      (node (ref "U12") (pin "6") (pinfunction "I6_6") (pintype "input"))
    )
    (net (code "118") (name "Net-(U11A-QG)") (class "Default")
      (node (ref "R53") (pin "1") (pinfunction "1_1") (pintype "passive"))
      (node (ref "U11") (pin "6") (pinfunction "QG_6") (pintype "tri_state"))
      (node (ref "U12") (pin "7") (pinfunction "I7_7") (pintype "input"))
    )
    (net (code "119") (name "Net-(U11A-QH)") (class "Default")
      (node (ref "R52") (pin "1") (pinfunction "1_1") (pintype "passive"))
      (node (ref "U11") (pin "7") (pinfunction "QH_7") (pintype "tri_state"))
      (node (ref "U12") (pin "8") (pinfunction "I8_8") (pintype "input"))
    )
    (net (code "120") (name "Net-(U13A-QA)") (class "Default")
      (node (ref "R67") (pin "1") (pinfunction "1_1") (pintype "passive"))
      (node (ref "U13") (pin "15") (pinfunction "QA_15") (pintype "tri_state"))
      (node (ref "U14") (pin "1") (pinfunction "I1_1") (pintype "input"))
    )
    (net (code "121") (name "Net-(U13A-QB)") (class "Default")
      (node (ref "R66") (pin "1") (pinfunction "1_1") (pintype "passive"))
      (node (ref "U13") (pin "1") (pinfunction "QB_1") (pintype "tri_state"))
      (node (ref "U14") (pin "2") (pinfunction "I2_2") (pintype "input"))
    )
    (net (code "122") (name "Net-(U13A-QC)") (class "Default")
      (node (ref "R65") (pin "1") (pinfunction "1_1") (pintype "passive"))
      (node (ref "U13") (pin "2") (pinfunction "QC_2") (pintype "tri_state"))
      (node (ref "U14") (pin "3") (pinfunction "I3_3") (pintype "input"))
    )
    (net (code "123") (name "Net-(U13A-QD)") (class "Default")
      (node (ref "R64") (pin "1") (pinfunction "1_1") (pintype "passive"))
      (node (ref "U13") (pin "3") (pinfunction "QD_3") (pintype "tri_state"))
      (node (ref "U14") (pin "4") (pinfunction "I4_4") (pintype "input"))
    )
    (net (code "124") (name "Net-(U13A-QE)") (class "Default")
      (node (ref "R63") (pin "1") (pinfunction "1_1") (pintype "passive"))
      (node (ref "U13") (pin "4") (pinfunction "QE_4") (pintype "tri_state"))
      (node (ref "U14") (pin "5") (pinfunction "I5_5") (pintype "input"))
    )
    (net (code "125") (name "Net-(U13A-QF)") (class "Default")
      (node (ref "R62") (pin "1") (pinfunction "1_1") (pintype "passive"))
      (node (ref "U13") (pin "5") (pinfunction "QF_5") (pintype "tri_state"))
      (node (ref "U14") (pin "6") (pinfunction "I6_6") (pintype "input"))
    )
    (net (code "126") (name "Net-(U13A-QG)") (class "Default")
      (node (ref "R61") (pin "1") (pinfunction "1_1") (pintype "passive"))
      (node (ref "U13") (pin "6") (pinfunction "QG_6") (pintype "tri_state"))
      (node (ref "U14") (pin "7") (pinfunction "I7_7") (pintype "input"))
    )
    (net (code "127") (name "Net-(U13A-QH)") (class "Default")
      (node (ref "R60") (pin "1") (pinfunction "1_1") (pintype "passive"))
      (node (ref "U13") (pin "7") (pinfunction "QH_7") (pintype "tri_state"))
      (node (ref "U14") (pin "8") (pinfunction "I8_8") (pintype "input"))
    )
    (net (code "128") (name "Net-(X1-Pad4)") (class "Default")
      (node (ref "X1") (pin "4") (pinfunction "4_4") (pintype "passive"))
      (node (ref "X2") (pin "4") (pinfunction "4_4") (pintype "passive"))
    )
    (net (code "129") (name "Net-(X1-Pad5)") (class "Default")
      (node (ref "X1") (pin "5") (pinfunction "5_5") (pintype "passive"))
      (node (ref "X2") (pin "5") (pinfunction "5_5") (pintype "passive"))
    )
    (net (code "130") (name "OLAT") (class "Default")
      (node (ref "G1") (pin "PA8") (pinfunction "PA8_PA8") (pintype "bidirectional"))
      (node (ref "R3") (pin "1") (pinfunction "1_1") (pintype "passive"))
      (node (ref "U11") (pin "12") (pinfunction "RCK_12") (pintype "input"))
      (node (ref "U13") (pin "12") (pinfunction "RCK_12") (pintype "input"))
    )
    (net (code "131") (name "SCK") (class "Default")
      (node (ref "G1") (pin "PB3") (pinfunction "PB3_PB3") (pintype "bidirectional"))
      (node (ref "JP5") (pin "3") (pinfunction "3_3") (pintype "passive"))
      (node (ref "R5") (pin "1") (pinfunction "1_1") (pintype "passive"))
      (node (ref "U11") (pin "11") (pinfunction "SCK_11") (pintype "input"))
      (node (ref "U13") (pin "11") (pinfunction "SCK_11") (pintype "input"))
    )
    (net (code "132") (name "SCK2") (class "Default")
      (node (ref "G1") (pin "PB10") (pinfunction "PB10_PB10") (pintype "bidirectional"))
      (node (ref "SJ20") (pin "P$1") (pinfunction "1_P$1") (pintype "passive"))
      (node (ref "U3") (pin "7") (pinfunction "CLK_7") (pintype "input"))
      (node (ref "U4") (pin "7") (pinfunction "CLK_7") (pintype "input"))
    )
    (net (code "133") (name "SLNK1") (class "Default")
      (node (ref "SJ13") (pin "P$1") (pinfunction "1_P$1") (pintype "passive"))
      (node (ref "U11") (pin "14") (pinfunction "SER_14") (pintype "input"))
      (node (ref "U13") (pin "9") (pinfunction "QH*_9") (pintype "tri_state"))
    )
    (net (code "134") (name "SLNK2") (class "Default")
      (node (ref "SJ4") (pin "P$1") (pinfunction "1_P$1") (pintype "passive"))
      (node (ref "U11") (pin "9") (pinfunction "QH*_9") (pintype "tri_state"))
    )
    (net (code "135") (name "SLNK3") (class "Default")
      (node (ref "SJ6") (pin "P$1") (pinfunction "1_P$1") (pintype "passive"))
      (node (ref "U3") (pin "1") (pinfunction "SER_1") (pintype "input"))
      (node (ref "U4") (pin "13") (pinfunction "QH_13") (pintype "output"))
    )
    (net (code "136") (name "SRV1") (class "Default")
      (node (ref "G1") (pin "PC9") (pinfunction "PC9_PC9") (pintype "bidirectional"))
      (node (ref "JP4") (pin "2") (pinfunction "2_2") (pintype "passive"))
      (node (ref "R13") (pin "2") (pinfunction "2_2") (pintype "passive"))
    )
    (net (code "137") (name "SRV2") (class "Default")
      (node (ref "G1") (pin "PC7") (pinfunction "PC7_PC7") (pintype "bidirectional"))
      (node (ref "JP4") (pin "1") (pinfunction "1_1") (pintype "passive"))
      (node (ref "R12") (pin "2") (pinfunction "2_2") (pintype "passive"))
    )
    (net (code "138") (name "SRV3") (class "Default")
      (node (ref "G1") (pin "PC8") (pinfunction "PC8_PC8") (pintype "bidirectional"))
      (node (ref "JP3") (pin "2") (pinfunction "2_2") (pintype "passive"))
      (node (ref "R11") (pin "2") (pinfunction "2_2") (pintype "passive"))
    )
    (net (code "139") (name "SRV4") (class "Default")
      (node (ref "G1") (pin "PC6") (pinfunction "PC6_PC6") (pintype "bidirectional"))
      (node (ref "JP3") (pin "1") (pinfunction "1_1") (pintype "passive"))
      (node (ref "R10") (pin "2") (pinfunction "2_2") (pintype "passive"))
    )
    (net (code "140") (name "SRV5") (class "Default")
      (node (ref "G1") (pin "PF1-PH1") (pinfunction "PF1-PH1_PF1-PH1") (pintype "bidirectional"))
      (node (ref "JP2") (pin "2") (pinfunction "2_2") (pintype "passive"))
      (node (ref "R9") (pin "2") (pinfunction "2_2") (pintype "passive"))
    )
    (net (code "141") (name "SRV6") (class "Default")
      (node (ref "G1") (pin "PA15") (pinfunction "PA15_PA15") (pintype "bidirectional"))
      (node (ref "JP2") (pin "1") (pinfunction "1_1") (pintype "passive"))
      (node (ref "R8") (pin "2") (pinfunction "2_2") (pintype "passive"))
    )
    (net (code "142") (name "SRV7") (class "Default")
      (node (ref "G1") (pin "PC12") (pinfunction "PC12_PC12") (pintype "bidirectional"))
      (node (ref "JP1") (pin "2") (pinfunction "2_2") (pintype "passive"))
      (node (ref "R7") (pin "2") (pinfunction "2_2") (pintype "passive"))
    )
    (net (code "143") (name "SRV8") (class "Default")
      (node (ref "G1") (pin "PD2") (pinfunction "PD2_PD2") (pintype "bidirectional"))
      (node (ref "JP1") (pin "1") (pinfunction "1_1") (pintype "passive"))
      (node (ref "R6") (pin "2") (pinfunction "2_2") (pintype "passive"))
    )
    (net (code "144") (name "TDRV1") (class "Default")
      (node (ref "G1") (pin "PB12") (pinfunction "PB12_PB12") (pintype "bidirectional"))
      (node (ref "U10") (pin "2") (pinfunction "I_2") (pintype "input"))
      (node (ref "U9") (pin "12") (pinfunction "+IN_12") (pintype "input"))
    )
    (net (code "145") (name "TDRV2") (class "Default")
      (node (ref "G1") (pin "PB2") (pinfunction "PB2_PB2") (pintype "bidirectional"))
      (node (ref "U10") (pin "4") (pinfunction "I_4") (pintype "input"))
      (node (ref "U9") (pin "3") (pinfunction "+IN_3") (pintype "input"))
    )
    (net (code "146") (name "TDRV3") (class "Default")
      (node (ref "G1") (pin "PB15") (pinfunction "PB15_PB15") (pintype "bidirectional"))
      (node (ref "U8") (pin "4") (pinfunction "I_4") (pintype "input"))
      (node (ref "U9") (pin "10") (pinfunction "+IN_10") (pintype "input"))
    )
    (net (code "147") (name "TDRV4") (class "Default")
      (node (ref "G1") (pin "PB1") (pinfunction "PB1_PB1") (pintype "bidirectional"))
      (node (ref "U8") (pin "2") (pinfunction "I_2") (pintype "input"))
      (node (ref "U9") (pin "5") (pinfunction "+IN_5") (pintype "input"))
    )
    (net (code "148") (name "TDRV5") (class "Default")
      (node (ref "G1") (pin "PA0") (pinfunction "PA0_PA0") (pintype "bidirectional"))
      (node (ref "U6") (pin "12") (pinfunction "+IN_12") (pintype "input"))
      (node (ref "U7") (pin "2") (pinfunction "I_2") (pintype "input"))
    )
    (net (code "149") (name "TDRV6") (class "Default")
      (node (ref "G1") (pin "PA4") (pinfunction "PA4_PA4") (pintype "bidirectional"))
      (node (ref "U6") (pin "3") (pinfunction "+IN_3") (pintype "input"))
      (node (ref "U7") (pin "4") (pinfunction "I_4") (pintype "input"))
    )
    (net (code "150") (name "TDRV7") (class "Default")
      (node (ref "G1") (pin "PC3") (pinfunction "PC3_PC3") (pintype "bidirectional"))
      (node (ref "U5") (pin "4") (pinfunction "I_4") (pintype "input"))
      (node (ref "U6") (pin "10") (pinfunction "+IN_10") (pintype "input"))
    )
    (net (code "151") (name "TDRV8") (class "Default")
      (node (ref "G1") (pin "PC0") (pinfunction "PC0_PC0") (pintype "bidirectional"))
      (node (ref "U5") (pin "2") (pinfunction "I_2") (pintype "input"))
      (node (ref "U6") (pin "5") (pinfunction "+IN_5") (pintype "input"))
    )
    (net (code "152") (name "V+") (class "Default")
      (node (ref "C6") (pin "+") (pinfunction "+_+") (pintype "passive"))
      (node (ref "C7") (pin "1") (pinfunction "1_1") (pintype "passive"))
      (node (ref "G1") (pin "E5V") (pinfunction "E5V_E5V") (pintype "power_in"))
      (node (ref "IC1") (pin "1") (pinfunction "FB_1") (pintype "input"))
      (node (ref "L1") (pin "1") (pinfunction "1_1") (pintype "passive"))
      (node (ref "U2") (pin "3") (pinfunction "FB_3") (pintype "bidirectional"))
    )
    (net (code "153") (name "unconnected-(G1-PadBOOT0)") (class "Default")
      (node (ref "G1") (pin "BOOT0") (pinfunction "BOOT0_BOOT0") (pintype "bidirectional"))
    )
    (net (code "154") (name "unconnected-(G1-PadIOREF2)") (class "Default")
      (node (ref "G1") (pin "IOREF2") (pinfunction "IOREF2_IOREF2") (pintype "input"))
    )
    (net (code "155") (name "unconnected-(G1-PadNC1-PF7)") (class "Default")
      (node (ref "G1") (pin "NC1-PF7") (pinfunction "NC1-PF7_NC1-PF7") (pintype "bidirectional"))
    )
    (net (code "156") (name "unconnected-(G1-PadNC2-PF6)") (class "Default")
      (node (ref "G1") (pin "NC2-PF6") (pinfunction "NC2-PF6_NC2-PF6") (pintype "bidirectional"))
    )
    (net (code "157") (name "unconnected-(G1-PadNC3)") (class "Default")
      (node (ref "G1") (pin "NC3") (pinfunction "NC3_NC3") (pintype "no_connect"))
    )
    (net (code "158") (name "unconnected-(G1-PadNC4)") (class "Default")
      (node (ref "G1") (pin "NC4") (pinfunction "NC4_NC4") (pintype "no_connect"))
    )
    (net (code "159") (name "unconnected-(G1-PadNC5-PD8)") (class "Default")
      (node (ref "G1") (pin "NC5-PD8") (pinfunction "NC5-PD8_NC5-PD8") (pintype "bidirectional"))
    )
    (net (code "160") (name "unconnected-(G1-PadNC6-PB11)") (class "Default")
      (node (ref "G1") (pin "NC6-PB11") (pinfunction "NC6-PB11_NC6-PB11") (pintype "no_connect"))
    )
    (net (code "161") (name "unconnected-(G1-PadNC7-PF5)") (class "Default")
      (node (ref "G1") (pin "NC7-PF5") (pinfunction "NC7-PF5_NC7-PF5") (pintype "bidirectional"))
    )
    (net (code "162") (name "unconnected-(G1-PadNC8-PF4)") (class "Default")
      (node (ref "G1") (pin "NC8-PF4") (pinfunction "NC8-PF4_NC8-PF4") (pintype "bidirectional"))
    )
    (net (code "163") (name "unconnected-(G1-PadNRESET)") (class "Default")
      (node (ref "G1") (pin "NRESET") (pinfunction "NRESET_NRESET") (pintype "input"))
    )
    (net (code "164") (name "unconnected-(G1-PadPA1)") (class "Default")
      (node (ref "G1") (pin "PA1") (pinfunction "PA1_PA1") (pintype "bidirectional"))
    )
    (net (code "165") (name "unconnected-(G1-PadPA2)") (class "Default")
      (node (ref "G1") (pin "PA2") (pinfunction "PA2_PA2") (pintype "bidirectional"))
    )
    (net (code "166") (name "unconnected-(G1-PadPA3)") (class "Default")
      (node (ref "G1") (pin "PA3") (pinfunction "PA3_PA3") (pintype "bidirectional"))
    )
    (net (code "167") (name "unconnected-(G1-PadPA5)") (class "Default")
      (node (ref "G1") (pin "PA5") (pinfunction "PA5_PA5") (pintype "bidirectional"))
    )
    (net (code "168") (name "unconnected-(G1-PadPA7)") (class "Default")
      (node (ref "G1") (pin "PA7") (pinfunction "PA7_PA7") (pintype "bidirectional"))
    )
    (net (code "169") (name "unconnected-(G1-PadPA9)") (class "Default")
      (node (ref "G1") (pin "PA9") (pinfunction "PA9_PA9") (pintype "bidirectional"))
    )
    (net (code "170") (name "unconnected-(G1-PadPA10)") (class "Default")
      (node (ref "G1") (pin "PA10") (pinfunction "PA10_PA10") (pintype "bidirectional"))
    )
    (net (code "171") (name "unconnected-(G1-PadPA11)") (class "Default")
      (node (ref "G1") (pin "PA11") (pinfunction "PA11_PA11") (pintype "bidirectional"))
    )
    (net (code "172") (name "unconnected-(G1-PadPA12)") (class "Default")
      (node (ref "G1") (pin "PA12") (pinfunction "PA12_PA12") (pintype "bidirectional"))
    )
    (net (code "173") (name "unconnected-(G1-PadPA13)") (class "Default")
      (node (ref "G1") (pin "PA13") (pinfunction "PA13_PA13") (pintype "bidirectional"))
    )
    (net (code "174") (name "unconnected-(G1-PadPA14)") (class "Default")
      (node (ref "G1") (pin "PA14") (pinfunction "PA14_PA14") (pintype "bidirectional"))
    )
    (net (code "175") (name "unconnected-(G1-PadPB0)") (class "Default")
      (node (ref "G1") (pin "PB0") (pinfunction "PB0_PB0") (pintype "bidirectional"))
    )
    (net (code "176") (name "unconnected-(G1-PadPC1)") (class "Default")
      (node (ref "G1") (pin "PC1") (pinfunction "PC1_PC1") (pintype "bidirectional"))
    )
    (net (code "177") (name "unconnected-(G1-PadPC4)") (class "Default")
      (node (ref "G1") (pin "PC4") (pinfunction "PC4_PC4") (pintype "bidirectional"))
    )
    (net (code "178") (name "unconnected-(G1-PadPC5)") (class "Default")
      (node (ref "G1") (pin "PC5") (pinfunction "PC5_PC5") (pintype "bidirectional"))
    )
    (net (code "179") (name "unconnected-(G1-PadPC13)") (class "Default")
      (node (ref "G1") (pin "PC13") (pinfunction "PC13_PC13") (pintype "bidirectional"))
    )
    (net (code "180") (name "unconnected-(G1-PadPC14)") (class "Default")
      (node (ref "G1") (pin "PC14") (pinfunction "PC14_PC14") (pintype "bidirectional"))
    )
    (net (code "181") (name "unconnected-(G1-PadPC15)") (class "Default")
      (node (ref "G1") (pin "PC15") (pinfunction "PC15_PC15") (pintype "bidirectional"))
    )
    (net (code "182") (name "unconnected-(G1-PadPF0-PH0)") (class "Default")
      (node (ref "G1") (pin "PF0-PH0") (pinfunction "PF0-PH0_PF0-PH0") (pintype "bidirectional"))
    )
    (net (code "183") (name "unconnected-(H1-MOUNT-PadB3,3)") (class "Default")
      (node (ref "H1") (pin "B3,3") (pinfunction "MOUNT_B3,3") (pintype "passive"))
    )
    (net (code "184") (name "unconnected-(H2-MOUNT-PadB3,3)") (class "Default")
      (node (ref "H2") (pin "B3,3") (pinfunction "MOUNT_B3,3") (pintype "passive"))
    )
    (net (code "185") (name "unconnected-(H3-MOUNT-PadB3,3)") (class "Default")
      (node (ref "H3") (pin "B3,3") (pinfunction "MOUNT_B3,3") (pintype "passive"))
    )
    (net (code "186") (name "unconnected-(H4-MOUNT-PadB3,3)") (class "Default")
      (node (ref "H4") (pin "B3,3") (pinfunction "MOUNT_B3,3") (pintype "passive"))
    )
  )
)
